# h11-5.net
KiCad netlist of a schematic drawn in EAGLE
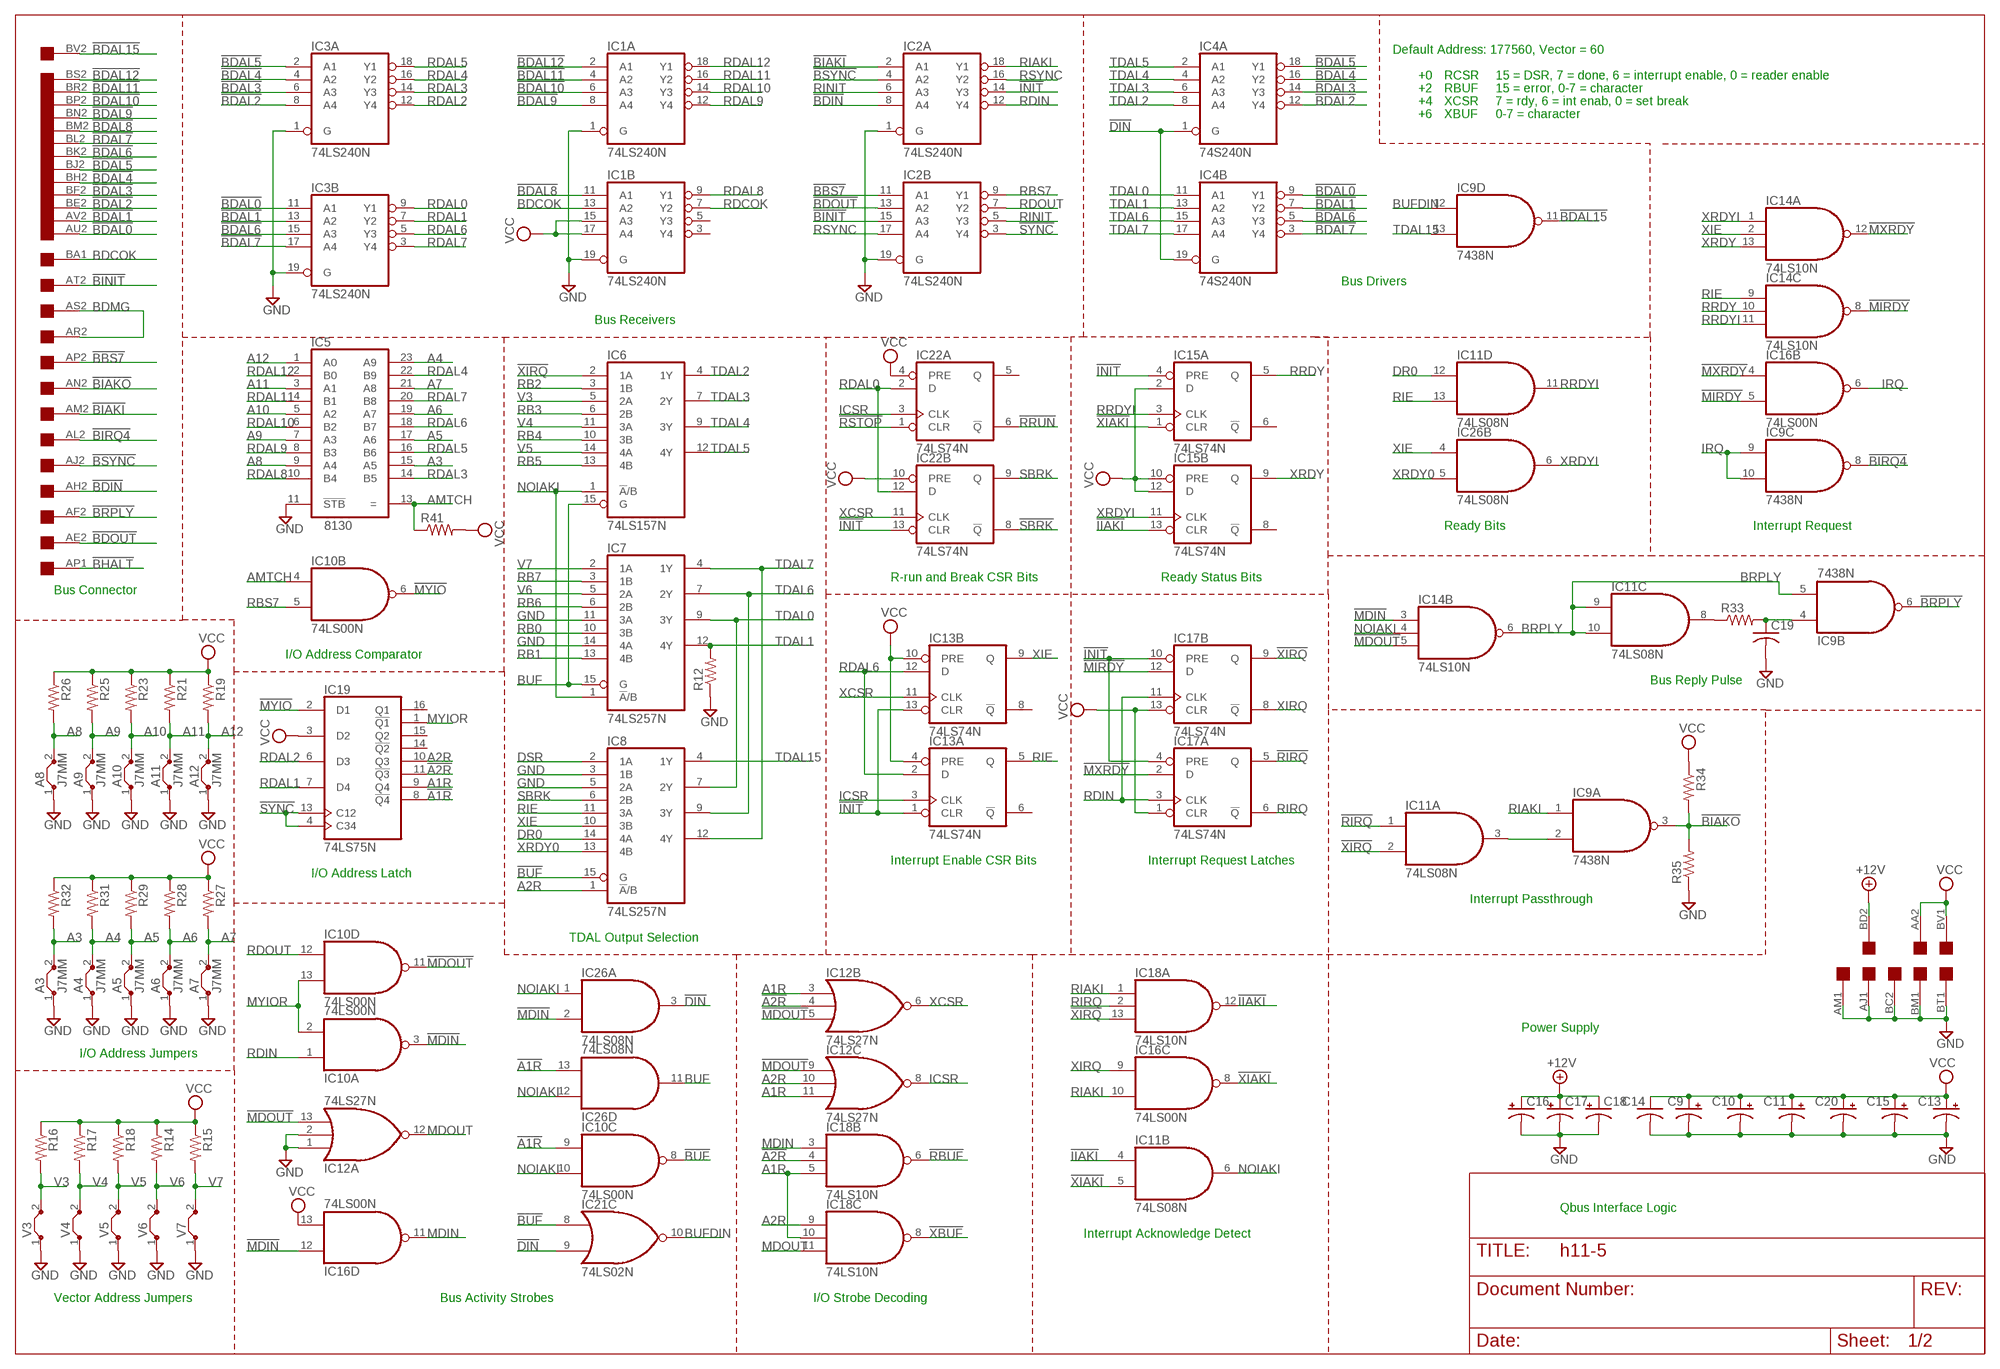
[diagram p0: schematic, sheet 1]
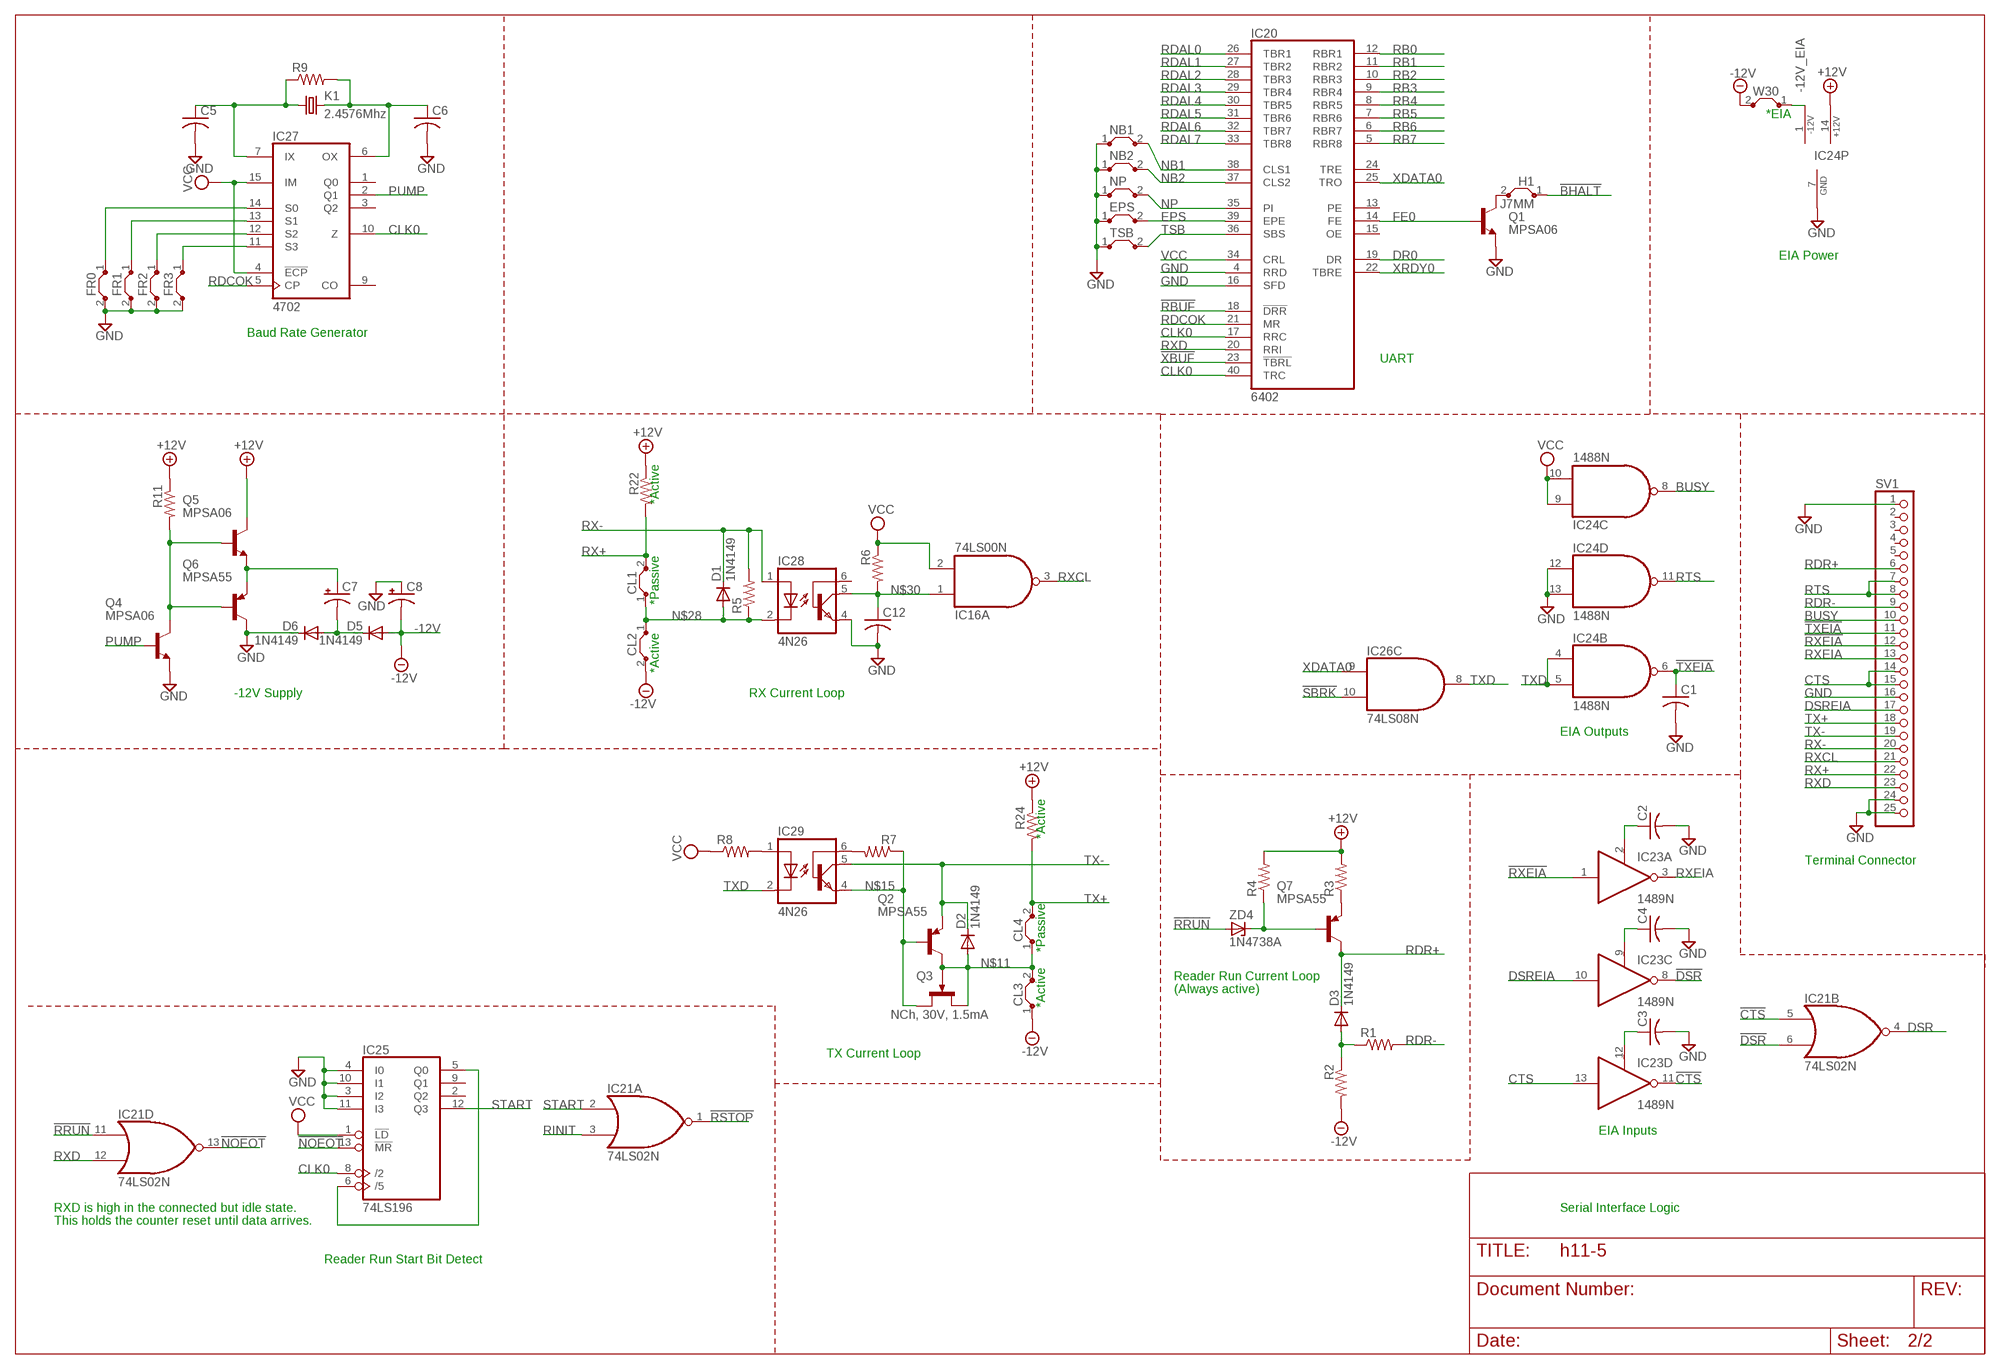
[diagram p1: schematic, sheet 2]

(export (version "E")
  (design (tool "Eeschema 10.0.6"))
  (components
    (comp (ref "C1")
      (value "C-US075-032X103")
      (footprint "eagle-import:C075-032X103")
      (libsource (lib "eagle-import") (part "C-US075-032X103"))
    )
    (comp (ref "C2")
      (value "C-US075-032X103")
      (footprint "eagle-import:C075-032X103")
      (libsource (lib "eagle-import") (part "C-US075-032X103"))
    )
    (comp (ref "C3")
      (value "C-US075-032X103")
      (footprint "eagle-import:C075-032X103")
      (libsource (lib "eagle-import") (part "C-US075-032X103"))
    )
    (comp (ref "C4")
      (value "C-US075-032X103")
      (footprint "eagle-import:C075-032X103")
      (libsource (lib "eagle-import") (part "C-US075-032X103"))
    )
    (comp (ref "C5")
      (value "C-US075-032X103")
      (footprint "eagle-import:C075-032X103")
      (libsource (lib "eagle-import") (part "C-US075-032X103"))
    )
    (comp (ref "C6")
      (value "C-US075-032X103")
      (footprint "eagle-import:C075-032X103")
      (libsource (lib "eagle-import") (part "C-US075-032X103"))
    )
    (comp (ref "C7")
      (value "CPOL-USB45181B")
      (footprint "eagle-import:B45181B")
      (libsource (lib "eagle-import") (part "CPOL-USB45181B"))
    )
    (comp (ref "C8")
      (value "CPOL-USB45181B")
      (footprint "eagle-import:B45181B")
      (libsource (lib "eagle-import") (part "CPOL-USB45181B"))
    )
    (comp (ref "C12")
      (value "C-US075-032X103")
      (footprint "eagle-import:C075-032X103")
      (libsource (lib "eagle-import") (part "C-US075-032X103"))
    )
    (comp (ref "CL1")
      (value "J7MM")
      (footprint "eagle-import:07")
      (libsource (lib "eagle-import") (part "J7MM"))
    )
    (comp (ref "CL2")
      (value "J7MM")
      (footprint "eagle-import:07")
      (libsource (lib "eagle-import") (part "J7MM"))
    )
    (comp (ref "CL3")
      (value "J7MM")
      (footprint "eagle-import:07")
      (libsource (lib "eagle-import") (part "J7MM"))
    )
    (comp (ref "CL4")
      (value "J7MM")
      (footprint "eagle-import:07")
      (libsource (lib "eagle-import") (part "J7MM"))
    )
    (comp (ref "D1")
      (value "1N4149")
      (footprint "eagle-import:DO35-10")
      (libsource (lib "eagle-import") (part "1N4148DO35-10"))
    )
    (comp (ref "D2")
      (value "1N4149")
      (footprint "eagle-import:DO35-10")
      (libsource (lib "eagle-import") (part "1N4148DO35-10"))
    )
    (comp (ref "D3")
      (value "1N4149")
      (footprint "eagle-import:DO35-10")
      (libsource (lib "eagle-import") (part "1N4148DO35-10"))
    )
    (comp (ref "D5")
      (value "1N4149")
      (footprint "eagle-import:DO35-10")
      (libsource (lib "eagle-import") (part "1N4148DO35-10"))
    )
    (comp (ref "D6")
      (value "1N4149")
      (footprint "eagle-import:DO35-10")
      (libsource (lib "eagle-import") (part "1N4148DO35-10"))
    )
    (comp (ref "EPS")
      (value "J7MM")
      (footprint "eagle-import:07")
      (libsource (lib "eagle-import") (part "J7MM"))
    )
    (comp (ref "FR0")
      (value "J7MM")
      (footprint "eagle-import:07")
      (libsource (lib "eagle-import") (part "J7MM"))
    )
    (comp (ref "FR1")
      (value "J7MM")
      (footprint "eagle-import:07")
      (libsource (lib "eagle-import") (part "J7MM"))
    )
    (comp (ref "FR2")
      (value "J7MM")
      (footprint "eagle-import:07")
      (libsource (lib "eagle-import") (part "J7MM"))
    )
    (comp (ref "FR3")
      (value "J7MM")
      (footprint "eagle-import:07")
      (libsource (lib "eagle-import") (part "J7MM"))
    )
    (comp (ref "H1")
      (value "J7MM")
      (footprint "eagle-import:07")
      (libsource (lib "eagle-import") (part "J7MM"))
    )
    (comp (ref "IC16")
      (value "74LS00N")
      (footprint "eagle-import:DIL14")
      (libsource (lib "eagle-import") (part "7400NLS"))
    )
    (comp (ref "IC20")
      (value "6402")
      (footprint "eagle-import:DIL40")
      (libsource (lib "eagle-import") (part "HD6402"))
    )
    (comp (ref "IC21")
      (value "74LS02N")
      (footprint "eagle-import:DIL14")
      (libsource (lib "eagle-import") (part "7402NLS"))
    )
    (comp (ref "IC23")
      (value "1489N")
      (footprint "eagle-import:DIL14")
      (libsource (lib "eagle-import") (part "1489N"))
    )
    (comp (ref "IC24")
      (value "1488N")
      (footprint "eagle-import:DIL14")
      (libsource (lib "eagle-import") (part "1488N"))
    )
    (comp (ref "IC25")
      (value "74LS196")
      (footprint "eagle-import:DIL14")
      (libsource (lib "eagle-import") (part "74LS196"))
    )
    (comp (ref "IC26")
      (value "74LS08N")
      (footprint "eagle-import:DIL14")
      (libsource (lib "eagle-import") (part "7408NLS"))
    )
    (comp (ref "IC27")
      (value "4702")
      (footprint "eagle-import:DIL16")
      (libsource (lib "eagle-import") (part "HD4702"))
    )
    (comp (ref "IC28")
      (value "4N26")
      (footprint "eagle-import:DIL06")
      (fields (field (name "MF") "FAIRCHILD SEMICONDUCTOR") (field (name "MPN") "4N35"))
      (libsource (lib "eagle-import") (part "4N35"))
    )
    (comp (ref "IC29")
      (value "4N26")
      (footprint "eagle-import:DIL06")
      (fields (field (name "MF") "FAIRCHILD SEMICONDUCTOR") (field (name "MPN") "4N35"))
      (libsource (lib "eagle-import") (part "4N35"))
    )
    (comp (ref "K1")
      (value "2.4576Mhz")
      (footprint "eagle-import:HC33U-H")
      (libsource (lib "eagle-import") (part "CRYSTALHC33U-H"))
    )
    (comp (ref "NB1")
      (value "J7MM")
      (footprint "eagle-import:07")
      (libsource (lib "eagle-import") (part "J7MM"))
    )
    (comp (ref "NB2")
      (value "J7MM")
      (footprint "eagle-import:07")
      (libsource (lib "eagle-import") (part "J7MM"))
    )
    (comp (ref "NP")
      (value "J7MM")
      (footprint "eagle-import:07")
      (libsource (lib "eagle-import") (part "J7MM"))
    )
    (comp (ref "Q1")
      (value "MPSA06")
      (footprint "eagle-import:TO92L")
      (libsource (lib "eagle-import") (part "-NPN-TO92L"))
    )
    (comp (ref "Q2")
      (value "MPSA55")
      (footprint "eagle-import:TO92L")
      (libsource (lib "eagle-import") (part "-PNP-TO92L"))
    )
    (comp (ref "Q3")
      (value "NCh, 30V, 1.5mA")
      (footprint "eagle-import:TO18E")
      (libsource (lib "eagle-import") (part "2N4391"))
    )
    (comp (ref "Q4")
      (value "MPSA06")
      (footprint "eagle-import:TO92L")
      (libsource (lib "eagle-import") (part "-NPN-TO92L"))
    )
    (comp (ref "Q5")
      (value "MPSA06")
      (footprint "eagle-import:TO92L")
      (libsource (lib "eagle-import") (part "-NPN-TO92L"))
    )
    (comp (ref "Q6")
      (value "MPSA55")
      (footprint "eagle-import:TO92L")
      (libsource (lib "eagle-import") (part "-PNP-TO92L"))
    )
    (comp (ref "Q7")
      (value "MPSA55")
      (footprint "eagle-import:TO92L")
      (libsource (lib "eagle-import") (part "-PNP-TO92L"))
    )
    (comp (ref "R1")
      (value "R-US_0207/10")
      (footprint "eagle-import:0207_10")
      (libsource (lib "eagle-import") (part "R-US_0207/10"))
    )
    (comp (ref "R2")
      (value "R-US_0207/10")
      (footprint "eagle-import:0207_10")
      (libsource (lib "eagle-import") (part "R-US_0207/10"))
    )
    (comp (ref "R3")
      (value "R-US_0207/10")
      (footprint "eagle-import:0207_10")
      (libsource (lib "eagle-import") (part "R-US_0207/10"))
    )
    (comp (ref "R4")
      (value "R-US_0207/10")
      (footprint "eagle-import:0207_10")
      (libsource (lib "eagle-import") (part "R-US_0207/10"))
    )
    (comp (ref "R5")
      (value "R-US_0207/10")
      (footprint "eagle-import:0207_10")
      (libsource (lib "eagle-import") (part "R-US_0207/10"))
    )
    (comp (ref "R6")
      (value "R-US_0207/10")
      (footprint "eagle-import:0207_10")
      (libsource (lib "eagle-import") (part "R-US_0207/10"))
    )
    (comp (ref "R7")
      (value "R-US_0207/10")
      (footprint "eagle-import:0207_10")
      (libsource (lib "eagle-import") (part "R-US_0207/10"))
    )
    (comp (ref "R8")
      (value "R-US_0207/10")
      (footprint "eagle-import:0207_10")
      (libsource (lib "eagle-import") (part "R-US_0207/10"))
    )
    (comp (ref "R9")
      (value "R-US_0207/10")
      (footprint "eagle-import:0207_10")
      (libsource (lib "eagle-import") (part "R-US_0207/10"))
    )
    (comp (ref "R11")
      (value "R-US_0411/12")
      (footprint "eagle-import:0411_12")
      (libsource (lib "eagle-import") (part "R-US_0411/12"))
    )
    (comp (ref "R22")
      (value "R-US_0207/10")
      (footprint "eagle-import:0207_10")
      (libsource (lib "eagle-import") (part "R-US_0207/10"))
    )
    (comp (ref "R24")
      (value "R-US_0207/10")
      (footprint "eagle-import:0207_10")
      (libsource (lib "eagle-import") (part "R-US_0207/10"))
    )
    (comp (ref "SV1")
      (value "PINHD-1X25")
      (footprint "eagle-import:1X25")
      (libsource (lib "eagle-import") (part "PINHD-1X25"))
    )
    (comp (ref "TSB")
      (value "J7MM")
      (footprint "eagle-import:07")
      (libsource (lib "eagle-import") (part "J7MM"))
    )
    (comp (ref "W30")
      (value "J7MM")
      (footprint "eagle-import:07")
      (libsource (lib "eagle-import") (part "J7MM"))
    )
    (comp (ref "ZD4")
      (value "1N4738A")
      (footprint "eagle-import:DO41Z10")
      (libsource (lib "eagle-import") (part "1N4728"))
    )
    (comp (ref "A3")
      (value "J7MM")
      (footprint "eagle-import:07")
      (libsource (lib "eagle-import") (part "J7MM"))
    )
    (comp (ref "A4")
      (value "J7MM")
      (footprint "eagle-import:07")
      (libsource (lib "eagle-import") (part "J7MM"))
    )
    (comp (ref "A5")
      (value "J7MM")
      (footprint "eagle-import:07")
      (libsource (lib "eagle-import") (part "J7MM"))
    )
    (comp (ref "A6")
      (value "J7MM")
      (footprint "eagle-import:07")
      (libsource (lib "eagle-import") (part "J7MM"))
    )
    (comp (ref "A7")
      (value "J7MM")
      (footprint "eagle-import:07")
      (libsource (lib "eagle-import") (part "J7MM"))
    )
    (comp (ref "A8")
      (value "J7MM")
      (footprint "eagle-import:07")
      (libsource (lib "eagle-import") (part "J7MM"))
    )
    (comp (ref "A9")
      (value "J7MM")
      (footprint "eagle-import:07")
      (libsource (lib "eagle-import") (part "J7MM"))
    )
    (comp (ref "A10")
      (value "J7MM")
      (footprint "eagle-import:07")
      (libsource (lib "eagle-import") (part "J7MM"))
    )
    (comp (ref "A11")
      (value "J7MM")
      (footprint "eagle-import:07")
      (libsource (lib "eagle-import") (part "J7MM"))
    )
    (comp (ref "A12")
      (value "J7MM")
      (footprint "eagle-import:07")
      (libsource (lib "eagle-import") (part "J7MM"))
    )
    (comp (ref "C9")
      (value "CPOL-USB45181B")
      (footprint "eagle-import:B45181B")
      (libsource (lib "eagle-import") (part "CPOL-USB45181B"))
    )
    (comp (ref "C10")
      (value "CPOL-USB45181B")
      (footprint "eagle-import:B45181B")
      (libsource (lib "eagle-import") (part "CPOL-USB45181B"))
    )
    (comp (ref "C11")
      (value "CPOL-USB45181B")
      (footprint "eagle-import:B45181B")
      (libsource (lib "eagle-import") (part "CPOL-USB45181B"))
    )
    (comp (ref "C13")
      (value "CPOL-USB45181B")
      (footprint "eagle-import:B45181B")
      (libsource (lib "eagle-import") (part "CPOL-USB45181B"))
    )
    (comp (ref "C14")
      (value "C-US075-032X103")
      (footprint "eagle-import:C075-032X103")
      (libsource (lib "eagle-import") (part "C-US075-032X103"))
    )
    (comp (ref "C15")
      (value "CPOL-USB45181B")
      (footprint "eagle-import:B45181B")
      (libsource (lib "eagle-import") (part "CPOL-USB45181B"))
    )
    (comp (ref "C16")
      (value "CPOL-USB45181B")
      (footprint "eagle-import:B45181B")
      (libsource (lib "eagle-import") (part "CPOL-USB45181B"))
    )
    (comp (ref "C17")
      (value "CPOL-USB45181B")
      (footprint "eagle-import:B45181B")
      (libsource (lib "eagle-import") (part "CPOL-USB45181B"))
    )
    (comp (ref "C18")
      (value "CPOL-USB45181B")
      (footprint "eagle-import:B45181B")
      (libsource (lib "eagle-import") (part "CPOL-USB45181B"))
    )
    (comp (ref "C19")
      (value "C-US075-032X103")
      (footprint "eagle-import:C075-032X103")
      (libsource (lib "eagle-import") (part "C-US075-032X103"))
    )
    (comp (ref "C20")
      (value "CPOL-USB45181B")
      (footprint "eagle-import:B45181B")
      (libsource (lib "eagle-import") (part "CPOL-USB45181B"))
    )
    (comp (ref "EDGE$")
      (value "DOUBLE")
      (footprint "eagle-import:EDGE-CON4")
      (libsource (lib "eagle-import") (part "DOUBLE"))
    )
    (comp (ref "IC1")
      (value "74LS240N")
      (footprint "eagle-import:DIL20")
      (libsource (lib "eagle-import") (part "74240NLS"))
    )
    (comp (ref "IC2")
      (value "74LS240N")
      (footprint "eagle-import:DIL20")
      (libsource (lib "eagle-import") (part "74240NLS"))
    )
    (comp (ref "IC3")
      (value "74LS240N")
      (footprint "eagle-import:DIL20")
      (libsource (lib "eagle-import") (part "74240NLS"))
    )
    (comp (ref "IC4")
      (value "74S240N")
      (footprint "eagle-import:DIL20")
      (libsource (lib "eagle-import") (part "74240NS"))
    )
    (comp (ref "IC5")
      (value "8130")
      (footprint "eagle-import:DIL24")
      (libsource (lib "eagle-import") (part "8130"))
    )
    (comp (ref "IC6")
      (value "74LS157N")
      (footprint "eagle-import:DIL16")
      (libsource (lib "eagle-import") (part "74157NLS"))
    )
    (comp (ref "IC7")
      (value "74LS257N")
      (footprint "eagle-import:DIL16")
      (libsource (lib "eagle-import") (part "74257NLS"))
    )
    (comp (ref "IC8")
      (value "74LS257N")
      (footprint "eagle-import:DIL16")
      (libsource (lib "eagle-import") (part "74257NLS"))
    )
    (comp (ref "IC9")
      (value "7438N")
      (footprint "eagle-import:DIL14")
      (libsource (lib "eagle-import") (part "7438NLS"))
    )
    (comp (ref "IC10")
      (value "74LS00N")
      (footprint "eagle-import:DIL14")
      (libsource (lib "eagle-import") (part "7400NLS"))
    )
    (comp (ref "IC11")
      (value "74LS08N")
      (footprint "eagle-import:DIL14")
      (libsource (lib "eagle-import") (part "7408NLS"))
    )
    (comp (ref "IC12")
      (value "74LS27N")
      (footprint "eagle-import:DIL14")
      (libsource (lib "eagle-import") (part "7427NLS"))
    )
    (comp (ref "IC13")
      (value "74LS74N")
      (footprint "eagle-import:DIL14")
      (libsource (lib "eagle-import") (part "7474NLS"))
    )
    (comp (ref "IC14")
      (value "74LS10N")
      (footprint "eagle-import:DIL14")
      (libsource (lib "eagle-import") (part "7410NLS"))
    )
    (comp (ref "IC15")
      (value "74LS74N")
      (footprint "eagle-import:DIL14")
      (libsource (lib "eagle-import") (part "7474NLS"))
    )
    (comp (ref "IC17")
      (value "74LS74N")
      (footprint "eagle-import:DIL14")
      (libsource (lib "eagle-import") (part "7474NLS"))
    )
    (comp (ref "IC18")
      (value "74LS10N")
      (footprint "eagle-import:DIL14")
      (libsource (lib "eagle-import") (part "7410NLS"))
    )
    (comp (ref "IC19")
      (value "74LS75N")
      (footprint "eagle-import:DIL16")
      (libsource (lib "eagle-import") (part "7475NLS"))
    )
    (comp (ref "IC22")
      (value "74LS74N")
      (footprint "eagle-import:DIL14")
      (libsource (lib "eagle-import") (part "7474NLS"))
    )
    (comp (ref "R12")
      (value "R-US_0207/10")
      (footprint "eagle-import:0207_10")
      (libsource (lib "eagle-import") (part "R-US_0207/10"))
    )
    (comp (ref "R14")
      (value "R-US_0207/10")
      (footprint "eagle-import:0207_10")
      (libsource (lib "eagle-import") (part "R-US_0207/10"))
    )
    (comp (ref "R15")
      (value "R-US_0207/10")
      (footprint "eagle-import:0207_10")
      (libsource (lib "eagle-import") (part "R-US_0207/10"))
    )
    (comp (ref "R16")
      (value "R-US_0207/10")
      (footprint "eagle-import:0207_10")
      (libsource (lib "eagle-import") (part "R-US_0207/10"))
    )
    (comp (ref "R17")
      (value "R-US_0207/10")
      (footprint "eagle-import:0207_10")
      (libsource (lib "eagle-import") (part "R-US_0207/10"))
    )
    (comp (ref "R18")
      (value "R-US_0207/10")
      (footprint "eagle-import:0207_10")
      (libsource (lib "eagle-import") (part "R-US_0207/10"))
    )
    (comp (ref "R19")
      (value "R-US_0207/10")
      (footprint "eagle-import:0207_10")
      (libsource (lib "eagle-import") (part "R-US_0207/10"))
    )
    (comp (ref "R21")
      (value "R-US_0207/10")
      (footprint "eagle-import:0207_10")
      (libsource (lib "eagle-import") (part "R-US_0207/10"))
    )
    (comp (ref "R23")
      (value "R-US_0207/10")
      (footprint "eagle-import:0207_10")
      (libsource (lib "eagle-import") (part "R-US_0207/10"))
    )
    (comp (ref "R25")
      (value "R-US_0207/10")
      (footprint "eagle-import:0207_10")
      (libsource (lib "eagle-import") (part "R-US_0207/10"))
    )
    (comp (ref "R26")
      (value "R-US_0207/10")
      (footprint "eagle-import:0207_10")
      (libsource (lib "eagle-import") (part "R-US_0207/10"))
    )
    (comp (ref "R27")
      (value "R-US_0207/10")
      (footprint "eagle-import:0207_10")
      (libsource (lib "eagle-import") (part "R-US_0207/10"))
    )
    (comp (ref "R28")
      (value "R-US_0207/10")
      (footprint "eagle-import:0207_10")
      (libsource (lib "eagle-import") (part "R-US_0207/10"))
    )
    (comp (ref "R29")
      (value "R-US_0207/10")
      (footprint "eagle-import:0207_10")
      (libsource (lib "eagle-import") (part "R-US_0207/10"))
    )
    (comp (ref "R31")
      (value "R-US_0207/10")
      (footprint "eagle-import:0207_10")
      (libsource (lib "eagle-import") (part "R-US_0207/10"))
    )
    (comp (ref "R32")
      (value "R-US_0207/10")
      (footprint "eagle-import:0207_10")
      (libsource (lib "eagle-import") (part "R-US_0207/10"))
    )
    (comp (ref "R33")
      (value "R-US_0207/10")
      (footprint "eagle-import:0207_10")
      (libsource (lib "eagle-import") (part "R-US_0207/10"))
    )
    (comp (ref "R34")
      (value "R-US_0207/10")
      (footprint "eagle-import:0207_10")
      (libsource (lib "eagle-import") (part "R-US_0207/10"))
    )
    (comp (ref "R35")
      (value "R-US_0207/10")
      (footprint "eagle-import:0207_10")
      (libsource (lib "eagle-import") (part "R-US_0207/10"))
    )
    (comp (ref "R41")
      (value "R-US_0207/10")
      (footprint "eagle-import:0207_10")
      (libsource (lib "eagle-import") (part "R-US_0207/10"))
    )
    (comp (ref "V3")
      (value "J7MM")
      (footprint "eagle-import:07")
      (libsource (lib "eagle-import") (part "J7MM"))
    )
    (comp (ref "V4")
      (value "J7MM")
      (footprint "eagle-import:07")
      (libsource (lib "eagle-import") (part "J7MM"))
    )
    (comp (ref "V5")
      (value "J7MM")
      (footprint "eagle-import:07")
      (libsource (lib "eagle-import") (part "J7MM"))
    )
    (comp (ref "V6")
      (value "J7MM")
      (footprint "eagle-import:07")
      (libsource (lib "eagle-import") (part "J7MM"))
    )
    (comp (ref "V7")
      (value "J7MM")
      (footprint "eagle-import:07")
      (libsource (lib "eagle-import") (part "J7MM"))
    )
  )
  (nets
    (net (code "1") (name "+12V") (class "Default")
      (node (ref "C16") (pin "+") (pinfunction "+_+") (pintype "passive"))
      (node (ref "C17") (pin "+") (pinfunction "+_+") (pintype "passive"))
      (node (ref "C18") (pin "+") (pinfunction "+_+") (pintype "passive"))
      (node (ref "EDGE$") (pin "BD2") (pinfunction "1_BD2") (pintype "bidirectional"))
      (node (ref "IC24") (pin "14") (pinfunction "+12V_14") (pintype "power_in"))
      (node (ref "Q5") (pin "3") (pinfunction "C_3") (pintype "passive"))
      (node (ref "R11") (pin "1") (pinfunction "1_1") (pintype "passive"))
      (node (ref "R22") (pin "1") (pinfunction "1_1") (pintype "passive"))
      (node (ref "R24") (pin "1") (pinfunction "1_1") (pintype "passive"))
      (node (ref "R3") (pin "2") (pinfunction "2_2") (pintype "passive"))
      (node (ref "R4") (pin "2") (pinfunction "2_2") (pintype "passive"))
    )
    (net (code "2") (name "-12V") (class "Default")
      (node (ref "C8") (pin "-") (pinfunction "-_-") (pintype "passive"))
      (node (ref "CL2") (pin "2") (pinfunction "2_2") (pintype "passive"))
      (node (ref "CL3") (pin "1") (pinfunction "1_1") (pintype "passive"))
      (node (ref "D5") (pin "A") (pinfunction "A_A") (pintype "passive"))
      (node (ref "R2") (pin "2") (pinfunction "2_2") (pintype "passive"))
      (node (ref "W30") (pin "2") (pinfunction "2_2") (pintype "passive"))
    )
    (net (code "3") (name "-12V_EIA") (class "Default")
      (node (ref "IC24") (pin "1") (pinfunction "-12V_1") (pintype "power_in"))
      (node (ref "W30") (pin "1") (pinfunction "1_1") (pintype "passive"))
    )
    (net (code "4") (name "A1R") (class "Default")
      (node (ref "IC12") (pin "11") (pinfunction "I2_11") (pintype "input"))
      (node (ref "IC12") (pin "3") (pinfunction "I0_3") (pintype "input"))
      (node (ref "IC18") (pin "10") (pinfunction "I1_10") (pintype "input"))
      (node (ref "IC18") (pin "5") (pinfunction "I2_5") (pintype "input"))
      (node (ref "IC19") (pin "9") (pinfunction "Q4_9") (pintype "output"))
    )
    (net (code "5") (name "A2R") (class "Default")
      (node (ref "IC12") (pin "10") (pinfunction "I1_10") (pintype "input"))
      (node (ref "IC18") (pin "9") (pinfunction "I0_9") (pintype "input"))
      (node (ref "IC19") (pin "10") (pinfunction "Q3_10") (pintype "output"))
      (node (ref "IC8") (pin "1") (pinfunction "~{A}/B_1") (pintype "input"))
    )
    (net (code "6") (name "A3") (class "Default")
      (node (ref "A3") (pin "2") (pinfunction "2_2") (pintype "passive"))
      (node (ref "IC5") (pin "15") (pinfunction "A5_15") (pintype "input"))
      (node (ref "R32") (pin "2") (pinfunction "2_2") (pintype "passive"))
    )
    (net (code "7") (name "A4") (class "Default")
      (node (ref "A4") (pin "2") (pinfunction "2_2") (pintype "passive"))
      (node (ref "IC5") (pin "23") (pinfunction "A9_23") (pintype "input"))
      (node (ref "R31") (pin "2") (pinfunction "2_2") (pintype "passive"))
    )
    (net (code "8") (name "A5") (class "Default")
      (node (ref "A5") (pin "2") (pinfunction "2_2") (pintype "passive"))
      (node (ref "IC5") (pin "17") (pinfunction "A6_17") (pintype "input"))
      (node (ref "R29") (pin "2") (pinfunction "2_2") (pintype "passive"))
    )
    (net (code "9") (name "A6") (class "Default")
      (node (ref "A6") (pin "2") (pinfunction "2_2") (pintype "passive"))
      (node (ref "IC5") (pin "19") (pinfunction "A7_19") (pintype "input"))
      (node (ref "R28") (pin "2") (pinfunction "2_2") (pintype "passive"))
    )
    (net (code "10") (name "A7") (class "Default")
      (node (ref "A7") (pin "2") (pinfunction "2_2") (pintype "passive"))
      (node (ref "IC5") (pin "21") (pinfunction "A8_21") (pintype "input"))
      (node (ref "R27") (pin "2") (pinfunction "2_2") (pintype "passive"))
    )
    (net (code "11") (name "A8") (class "Default")
      (node (ref "A8") (pin "2") (pinfunction "2_2") (pintype "passive"))
      (node (ref "IC5") (pin "9") (pinfunction "A4_9") (pintype "input"))
      (node (ref "R26") (pin "2") (pinfunction "2_2") (pintype "passive"))
    )
    (net (code "12") (name "A9") (class "Default")
      (node (ref "A9") (pin "2") (pinfunction "2_2") (pintype "passive"))
      (node (ref "IC5") (pin "7") (pinfunction "A3_7") (pintype "input"))
      (node (ref "R25") (pin "2") (pinfunction "2_2") (pintype "passive"))
    )
    (net (code "13") (name "A10") (class "Default")
      (node (ref "A10") (pin "2") (pinfunction "2_2") (pintype "passive"))
      (node (ref "IC5") (pin "5") (pinfunction "A2_5") (pintype "input"))
      (node (ref "R23") (pin "2") (pinfunction "2_2") (pintype "passive"))
    )
    (net (code "14") (name "A11") (class "Default")
      (node (ref "A11") (pin "2") (pinfunction "2_2") (pintype "passive"))
      (node (ref "IC5") (pin "3") (pinfunction "A1_3") (pintype "input"))
      (node (ref "R21") (pin "2") (pinfunction "2_2") (pintype "passive"))
    )
    (net (code "15") (name "A12") (class "Default")
      (node (ref "A12") (pin "2") (pinfunction "2_2") (pintype "passive"))
      (node (ref "IC5") (pin "1") (pinfunction "A0_1") (pintype "input"))
      (node (ref "R19") (pin "2") (pinfunction "2_2") (pintype "passive"))
    )
    (net (code "16") (name "AMTCH") (class "Default")
      (node (ref "IC10") (pin "4") (pinfunction "I0_4") (pintype "input"))
      (node (ref "IC5") (pin "13") (pinfunction "=_13") (pintype "output"))
      (node (ref "R41") (pin "1") (pinfunction "1_1") (pintype "passive"))
    )
    (net (code "17") (name "BDCOK") (class "Default")
      (node (ref "EDGE$") (pin "BA1") (pinfunction "1_BA1") (pintype "bidirectional"))
      (node (ref "IC1") (pin "13") (pinfunction "A2_13") (pintype "input"))
    )
    (net (code "18") (name "BDMG") (class "Default")
      (node (ref "EDGE$") (pin "AR2") (pinfunction "1_AR2") (pintype "bidirectional"))
      (node (ref "EDGE$") (pin "AS2") (pinfunction "1_AS2") (pintype "bidirectional"))
    )
    (net (code "19") (name "BRPLY") (class "Default")
      (node (ref "IC11") (pin "10") (pinfunction "I1_10") (pintype "input"))
      (node (ref "IC11") (pin "9") (pinfunction "I0_9") (pintype "input"))
      (node (ref "IC14") (pin "6") (pinfunction "O_6") (pintype "output"))
      (node (ref "IC9") (pin "5") (pinfunction "I1_5") (pintype "input"))
    )
    (net (code "20") (name "BUF") (class "Default")
      (node (ref "IC26") (pin "11") (pinfunction "O_11") (pintype "output"))
      (node (ref "IC6") (pin "15") (pinfunction "G_15") (pintype "input"))
      (node (ref "IC7") (pin "15") (pinfunction "G_15") (pintype "input"))
    )
    (net (code "21") (name "BUFDIN") (class "Default")
      (node (ref "IC21") (pin "10") (pinfunction "O_10") (pintype "output"))
      (node (ref "IC9") (pin "12") (pinfunction "I0_12") (pintype "input"))
    )
    (net (code "22") (name "BUSY") (class "Default")
      (node (ref "IC24") (pin "8") (pinfunction "O_8") (pintype "output"))
      (node (ref "SV1") (pin "10") (pinfunction "10_10") (pintype "passive"))
    )
    (net (code "23") (name "CLK0") (class "Default")
      (node (ref "IC20") (pin "17") (pinfunction "RRC_17") (pintype "input"))
      (node (ref "IC20") (pin "40") (pinfunction "TRC_40") (pintype "input"))
      (node (ref "IC25") (pin "8") (pinfunction "/2_8") (pintype "bidirectional"))
      (node (ref "IC27") (pin "10") (pinfunction "Z_10") (pintype "output"))
    )
    (net (code "24") (name "CTS") (class "Default")
      (node (ref "IC23") (pin "13") (pinfunction "I_13") (pintype "input"))
      (node (ref "SV1") (pin "14") (pinfunction "14_14") (pintype "passive"))
      (node (ref "SV1") (pin "15") (pinfunction "15_15") (pintype "passive"))
    )
    (net (code "25") (name "DR0") (class "Default")
      (node (ref "IC11") (pin "12") (pinfunction "I0_12") (pintype "input"))
      (node (ref "IC20") (pin "19") (pinfunction "DR_19") (pintype "tri_state"))
      (node (ref "IC8") (pin "14") (pinfunction "4A_14") (pintype "input"))
    )
    (net (code "26") (name "DSR") (class "Default")
      (node (ref "IC21") (pin "4") (pinfunction "O_4") (pintype "output"))
      (node (ref "IC8") (pin "2") (pinfunction "1A_2") (pintype "input"))
    )
    (net (code "27") (name "DSREIA") (class "Default")
      (node (ref "IC23") (pin "10") (pinfunction "I_10") (pintype "input"))
      (node (ref "SV1") (pin "17") (pinfunction "17_17") (pintype "passive"))
    )
    (net (code "28") (name "EPS") (class "Default")
      (node (ref "EPS") (pin "2") (pinfunction "2_2") (pintype "passive"))
      (node (ref "IC20") (pin "39") (pinfunction "EPE_39") (pintype "input"))
    )
    (net (code "29") (name "FE0") (class "Default")
      (node (ref "IC20") (pin "14") (pinfunction "FE_14") (pintype "tri_state"))
      (node (ref "Q1") (pin "2") (pinfunction "B_2") (pintype "passive"))
    )
    (net (code "30") (name "GND") (class "Default")
      (node (ref "A10") (pin "1") (pinfunction "1_1") (pintype "passive"))
      (node (ref "A11") (pin "1") (pinfunction "1_1") (pintype "passive"))
      (node (ref "A12") (pin "1") (pinfunction "1_1") (pintype "passive"))
      (node (ref "A3") (pin "1") (pinfunction "1_1") (pintype "passive"))
      (node (ref "A4") (pin "1") (pinfunction "1_1") (pintype "passive"))
      (node (ref "A5") (pin "1") (pinfunction "1_1") (pintype "passive"))
      (node (ref "A6") (pin "1") (pinfunction "1_1") (pintype "passive"))
      (node (ref "A7") (pin "1") (pinfunction "1_1") (pintype "passive"))
      (node (ref "A8") (pin "1") (pinfunction "1_1") (pintype "passive"))
      (node (ref "A9") (pin "1") (pinfunction "1_1") (pintype "passive"))
      (node (ref "C1") (pin "2") (pinfunction "2_2") (pintype "passive"))
      (node (ref "C10") (pin "-") (pinfunction "-_-") (pintype "passive"))
      (node (ref "C11") (pin "-") (pinfunction "-_-") (pintype "passive"))
      (node (ref "C12") (pin "2") (pinfunction "2_2") (pintype "passive"))
      (node (ref "C13") (pin "-") (pinfunction "-_-") (pintype "passive"))
      (node (ref "C14") (pin "2") (pinfunction "2_2") (pintype "passive"))
      (node (ref "C15") (pin "-") (pinfunction "-_-") (pintype "passive"))
      (node (ref "C16") (pin "-") (pinfunction "-_-") (pintype "passive"))
      (node (ref "C17") (pin "-") (pinfunction "-_-") (pintype "passive"))
      (node (ref "C18") (pin "-") (pinfunction "-_-") (pintype "passive"))
      (node (ref "C19") (pin "2") (pinfunction "2_2") (pintype "passive"))
      (node (ref "C2") (pin "2") (pinfunction "2_2") (pintype "passive"))
      (node (ref "C20") (pin "-") (pinfunction "-_-") (pintype "passive"))
      (node (ref "C3") (pin "2") (pinfunction "2_2") (pintype "passive"))
      (node (ref "C4") (pin "2") (pinfunction "2_2") (pintype "passive"))
      (node (ref "C5") (pin "2") (pinfunction "2_2") (pintype "passive"))
      (node (ref "C6") (pin "2") (pinfunction "2_2") (pintype "passive"))
      (node (ref "C8") (pin "+") (pinfunction "+_+") (pintype "passive"))
      (node (ref "C9") (pin "-") (pinfunction "-_-") (pintype "passive"))
      (node (ref "D6") (pin "C") (pinfunction "C_C") (pintype "passive"))
      (node (ref "EDGE$") (pin "AJ1") (pinfunction "1_AJ1") (pintype "bidirectional"))
      (node (ref "EDGE$") (pin "AM1") (pinfunction "1_AM1") (pintype "bidirectional"))
      (node (ref "EDGE$") (pin "BC2") (pinfunction "1_BC2") (pintype "bidirectional"))
      (node (ref "EDGE$") (pin "BM1") (pinfunction "1_BM1") (pintype "bidirectional"))
      (node (ref "EDGE$") (pin "BT1") (pinfunction "1_BT1") (pintype "bidirectional"))
      (node (ref "EPS") (pin "1") (pinfunction "1_1") (pintype "passive"))
      (node (ref "FR0") (pin "2") (pinfunction "2_2") (pintype "passive"))
      (node (ref "FR1") (pin "2") (pinfunction "2_2") (pintype "passive"))
      (node (ref "FR2") (pin "2") (pinfunction "2_2") (pintype "passive"))
      (node (ref "FR3") (pin "2") (pinfunction "2_2") (pintype "passive"))
      (node (ref "IC1") (pin "1") (pinfunction "G_1") (pintype "input"))
      (node (ref "IC1") (pin "19") (pinfunction "G_19") (pintype "input"))
      (node (ref "IC12") (pin "1") (pinfunction "I0_1") (pintype "input"))
      (node (ref "IC12") (pin "2") (pinfunction "I1_2") (pintype "input"))
      (node (ref "IC2") (pin "1") (pinfunction "G_1") (pintype "input"))
      (node (ref "IC2") (pin "19") (pinfunction "G_19") (pintype "input"))
      (node (ref "IC20") (pin "16") (pinfunction "SFD_16") (pintype "input"))
      (node (ref "IC20") (pin "4") (pinfunction "RRD_4") (pintype "input"))
      (node (ref "IC24") (pin "12") (pinfunction "I0_12") (pintype "input"))
      (node (ref "IC24") (pin "13") (pinfunction "I1_13") (pintype "input"))
      (node (ref "IC24") (pin "7") (pinfunction "GND_7") (pintype "power_in"))
      (node (ref "IC25") (pin "10") (pinfunction "I1_10") (pintype "input"))
      (node (ref "IC25") (pin "11") (pinfunction "I3_11") (pintype "input"))
      (node (ref "IC25") (pin "3") (pinfunction "I2_3") (pintype "input"))
      (node (ref "IC25") (pin "4") (pinfunction "I0_4") (pintype "input"))
      (node (ref "IC28") (pin "4") (pinfunction "EMI_4") (pintype "passive"))
      (node (ref "IC3") (pin "1") (pinfunction "G_1") (pintype "input"))
      (node (ref "IC3") (pin "19") (pinfunction "G_19") (pintype "input"))
      (node (ref "IC5") (pin "11") (pinfunction "~{STB}_11") (pintype "input"))
      (node (ref "IC7") (pin "11") (pinfunction "3A_11") (pintype "input"))
      (node (ref "IC7") (pin "14") (pinfunction "4A_14") (pintype "input"))
      (node (ref "IC8") (pin "3") (pinfunction "1B_3") (pintype "input"))
      (node (ref "IC8") (pin "5") (pinfunction "2A_5") (pintype "input"))
      (node (ref "NB1") (pin "1") (pinfunction "1_1") (pintype "passive"))
      (node (ref "NB2") (pin "1") (pinfunction "1_1") (pintype "passive"))
      (node (ref "NP") (pin "1") (pinfunction "1_1") (pintype "passive"))
      (node (ref "Q1") (pin "1") (pinfunction "E_1") (pintype "passive"))
      (node (ref "Q4") (pin "1") (pinfunction "E_1") (pintype "passive"))
      (node (ref "Q6") (pin "3") (pinfunction "C_3") (pintype "passive"))
      (node (ref "R12") (pin "1") (pinfunction "1_1") (pintype "passive"))
      (node (ref "R35") (pin "1") (pinfunction "1_1") (pintype "passive"))
      (node (ref "SV1") (pin "1") (pinfunction "1_1") (pintype "passive"))
      (node (ref "SV1") (pin "16") (pinfunction "16_16") (pintype "passive"))
      (node (ref "SV1") (pin "24") (pinfunction "24_24") (pintype "passive"))
      (node (ref "SV1") (pin "25") (pinfunction "25_25") (pintype "passive"))
      (node (ref "TSB") (pin "1") (pinfunction "1_1") (pintype "passive"))
      (node (ref "V3") (pin "1") (pinfunction "1_1") (pintype "passive"))
      (node (ref "V4") (pin "1") (pinfunction "1_1") (pintype "passive"))
      (node (ref "V5") (pin "1") (pinfunction "1_1") (pintype "passive"))
      (node (ref "V6") (pin "1") (pinfunction "1_1") (pintype "passive"))
      (node (ref "V7") (pin "1") (pinfunction "1_1") (pintype "passive"))
    )
    (net (code "31") (name "ICSR") (class "Default")
      (node (ref "IC12") (pin "8") (pinfunction "O_8") (pintype "output"))
      (node (ref "IC13") (pin "3") (pinfunction "CLK_3") (pintype "input"))
      (node (ref "IC22") (pin "3") (pinfunction "CLK_3") (pintype "input"))
    )
    (net (code "32") (name "IRQ") (class "Default")
      (node (ref "IC16") (pin "6") (pinfunction "O_6") (pintype "output"))
      (node (ref "IC9") (pin "10") (pinfunction "I1_10") (pintype "input"))
      (node (ref "IC9") (pin "9") (pinfunction "I0_9") (pintype "input"))
    )
    (net (code "33") (name "MDIN") (class "Default")
      (node (ref "IC16") (pin "11") (pinfunction "O_11") (pintype "output"))
      (node (ref "IC18") (pin "3") (pinfunction "I0_3") (pintype "input"))
    )
    (net (code "34") (name "MDOUT") (class "Default")
      (node (ref "IC12") (pin "12") (pinfunction "O_12") (pintype "output"))
      (node (ref "IC18") (pin "11") (pinfunction "I2_11") (pintype "input"))
    )
    (net (code "35") (name "MYIOR") (class "Default")
      (node (ref "IC10") (pin "13") (pinfunction "I1_13") (pintype "input"))
      (node (ref "IC10") (pin "2") (pinfunction "I1_2") (pintype "input"))
      (node (ref "IC19") (pin "1") (pinfunction "~{Q1}_1") (pintype "output"))
    )
    (net (code "36") (name "N$11") (class "Default")
      (node (ref "CL3") (pin "2") (pinfunction "2_2") (pintype "passive"))
      (node (ref "CL4") (pin "1") (pinfunction "1_1") (pintype "passive"))
      (node (ref "D2") (pin "A") (pinfunction "A_A") (pintype "passive"))
      (node (ref "Q2") (pin "3") (pinfunction "C_3") (pintype "passive"))
      (node (ref "Q3") (pin "D") (pinfunction "D_D") (pintype "passive"))
      (node (ref "Q3") (pin "G") (pinfunction "G_G") (pintype "passive"))
    )
    (net (code "37") (name "N$15") (class "Default")
      (node (ref "IC29") (pin "4") (pinfunction "EMI_4") (pintype "passive"))
      (node (ref "Q2") (pin "2") (pinfunction "B_2") (pintype "passive"))
      (node (ref "Q3") (pin "S") (pinfunction "S_S") (pintype "passive"))
      (node (ref "R7") (pin "1") (pinfunction "1_1") (pintype "passive"))
    )
    (net (code "38") (name "N$28") (class "Default")
      (node (ref "CL1") (pin "1") (pinfunction "1_1") (pintype "passive"))
      (node (ref "CL2") (pin "1") (pinfunction "1_1") (pintype "passive"))
      (node (ref "D1") (pin "A") (pinfunction "A_A") (pintype "passive"))
      (node (ref "IC28") (pin "2") (pinfunction "C_2") (pintype "passive"))
      (node (ref "R5") (pin "1") (pinfunction "1_1") (pintype "passive"))
    )
    (net (code "39") (name "N$30") (class "Default")
      (node (ref "C12") (pin "1") (pinfunction "1_1") (pintype "passive"))
      (node (ref "IC16") (pin "1") (pinfunction "I0_1") (pintype "input"))
      (node (ref "IC28") (pin "5") (pinfunction "COL_5") (pintype "passive"))
      (node (ref "R6") (pin "2") (pinfunction "2_2") (pintype "passive"))
    )
    (net (code "40") (name "NB1") (class "Default")
      (node (ref "IC20") (pin "38") (pinfunction "CLS1_38") (pintype "input"))
      (node (ref "NB1") (pin "2") (pinfunction "2_2") (pintype "passive"))
    )
    (net (code "41") (name "NB2") (class "Default")
      (node (ref "IC20") (pin "37") (pinfunction "CLS2_37") (pintype "input"))
      (node (ref "NB2") (pin "2") (pinfunction "2_2") (pintype "passive"))
    )
    (net (code "42") (name "NOIAKI") (class "Default")
      (node (ref "IC10") (pin "10") (pinfunction "I1_10") (pintype "input"))
      (node (ref "IC11") (pin "6") (pinfunction "O_6") (pintype "output"))
      (node (ref "IC14") (pin "4") (pinfunction "I1_4") (pintype "input"))
      (node (ref "IC26") (pin "1") (pinfunction "I0_1") (pintype "input"))
      (node (ref "IC26") (pin "12") (pinfunction "I0_12") (pintype "input"))
      (node (ref "IC6") (pin "1") (pinfunction "~{A}/B_1") (pintype "input"))
      (node (ref "IC7") (pin "1") (pinfunction "~{A}/B_1") (pintype "input"))
    )
    (net (code "43") (name "NP") (class "Default")
      (node (ref "IC20") (pin "35") (pinfunction "PI_35") (pintype "input"))
      (node (ref "NP") (pin "2") (pinfunction "2_2") (pintype "passive"))
    )
    (net (code "44") (name "Net-(C7-Pad-)") (class "Default")
      (node (ref "C7") (pin "-") (pinfunction "-_-") (pintype "passive"))
      (node (ref "D5") (pin "C") (pinfunction "C_C") (pintype "passive"))
      (node (ref "D6") (pin "A") (pinfunction "A_A") (pintype "passive"))
    )
    (net (code "45") (name "Net-(D3-PadA)") (class "Default")
      (node (ref "D3") (pin "A") (pinfunction "A_A") (pintype "passive"))
      (node (ref "R1") (pin "1") (pinfunction "1_1") (pintype "passive"))
      (node (ref "R2") (pin "1") (pinfunction "1_1") (pintype "passive"))
    )
    (net (code "46") (name "Net-(IC9B-I0)") (class "Default")
      (node (ref "C19") (pin "1") (pinfunction "1_1") (pintype "passive"))
      (node (ref "IC9") (pin "4") (pinfunction "I0_4") (pintype "input"))
      (node (ref "R33") (pin "2") (pinfunction "2_2") (pintype "passive"))
    )
    (net (code "47") (name "Net-(IC11A-O)") (class "Default")
      (node (ref "IC11") (pin "3") (pinfunction "O_3") (pintype "output"))
      (node (ref "IC9") (pin "2") (pinfunction "I1_2") (pintype "input"))
    )
    (net (code "48") (name "Net-(IC11C-O)") (class "Default")
      (node (ref "IC11") (pin "8") (pinfunction "O_8") (pintype "output"))
      (node (ref "R33") (pin "1") (pinfunction "1_1") (pintype "passive"))
    )
    (net (code "49") (name "Net-(IC23A-RC)") (class "Default")
      (node (ref "C2") (pin "1") (pinfunction "1_1") (pintype "passive"))
      (node (ref "IC23") (pin "2") (pinfunction "RC_2") (pintype "input"))
    )
    (net (code "50") (name "Net-(IC23C-RC)") (class "Default")
      (node (ref "C4") (pin "1") (pinfunction "1_1") (pintype "passive"))
      (node (ref "IC23") (pin "9") (pinfunction "RC_9") (pintype "input"))
    )
    (net (code "51") (name "Net-(IC23D-RC)") (class "Default")
      (node (ref "C3") (pin "1") (pinfunction "1_1") (pintype "passive"))
      (node (ref "IC23") (pin "12") (pinfunction "RC_12") (pintype "input"))
    )
    (net (code "52") (name "Net-(IC25A-Q0)") (class "Default")
      (node (ref "IC25") (pin "5") (pinfunction "Q0_5") (pintype "output"))
      (node (ref "IC25") (pin "6") (pinfunction "/5_6") (pintype "bidirectional"))
    )
    (net (code "53") (name "Net-(IC27A-IX)") (class "Default")
      (node (ref "C5") (pin "1") (pinfunction "1_1") (pintype "passive"))
      (node (ref "IC27") (pin "7") (pinfunction "IX_7") (pintype "input"))
      (node (ref "K1") (pin "1") (pinfunction "1_1") (pintype "passive"))
      (node (ref "R9") (pin "1") (pinfunction "1_1") (pintype "passive"))
    )
    (net (code "54") (name "Net-(IC27A-OX)") (class "Default")
      (node (ref "C6") (pin "1") (pinfunction "1_1") (pintype "passive"))
      (node (ref "IC27") (pin "6") (pinfunction "OX_6") (pintype "output"))
      (node (ref "K1") (pin "2") (pinfunction "2_2") (pintype "passive"))
      (node (ref "R9") (pin "2") (pinfunction "2_2") (pintype "passive"))
    )
    (net (code "55") (name "Net-(IC27A-S0)") (class "Default")
      (node (ref "FR0") (pin "1") (pinfunction "1_1") (pintype "passive"))
      (node (ref "IC27") (pin "14") (pinfunction "S0_14") (pintype "input"))
    )
    (net (code "56") (name "Net-(IC27A-S1)") (class "Default")
      (node (ref "FR1") (pin "1") (pinfunction "1_1") (pintype "passive"))
      (node (ref "IC27") (pin "13") (pinfunction "S1_13") (pintype "input"))
    )
    (net (code "57") (name "Net-(IC27A-S2)") (class "Default")
      (node (ref "FR2") (pin "1") (pinfunction "1_1") (pintype "passive"))
      (node (ref "IC27") (pin "12") (pinfunction "S2_12") (pintype "input"))
    )
    (net (code "58") (name "Net-(IC27A-S3)") (class "Default")
      (node (ref "FR3") (pin "1") (pinfunction "1_1") (pintype "passive"))
      (node (ref "IC27") (pin "11") (pinfunction "S3_11") (pintype "input"))
    )
    (net (code "59") (name "Net-(IC29-A)") (class "Default")
      (node (ref "IC29") (pin "1") (pinfunction "A_1") (pintype "passive"))
      (node (ref "R8") (pin "2") (pinfunction "2_2") (pintype "passive"))
    )
    (net (code "60") (name "Net-(IC29-BAS)") (class "Default")
      (node (ref "IC29") (pin "6") (pinfunction "BAS_6") (pintype "passive"))
      (node (ref "R7") (pin "2") (pinfunction "2_2") (pintype "passive"))
    )
    (net (code "61") (name "Net-(Q1-C)") (class "Default")
      (node (ref "H1") (pin "2") (pinfunction "2_2") (pintype "passive"))
      (node (ref "Q1") (pin "3") (pinfunction "C_3") (pintype "passive"))
    )
    (net (code "62") (name "Net-(Q4-C)") (class "Default")
      (node (ref "Q4") (pin "3") (pinfunction "C_3") (pintype "passive"))
      (node (ref "Q5") (pin "2") (pinfunction "B_2") (pintype "passive"))
      (node (ref "Q6") (pin "2") (pinfunction "B_2") (pintype "passive"))
      (node (ref "R11") (pin "2") (pinfunction "2_2") (pintype "passive"))
    )
    (net (code "63") (name "Net-(Q5-E)") (class "Default")
      (node (ref "C7") (pin "+") (pinfunction "+_+") (pintype "passive"))
      (node (ref "Q5") (pin "1") (pinfunction "E_1") (pintype "passive"))
      (node (ref "Q6") (pin "1") (pinfunction "E_1") (pintype "passive"))
    )
    (net (code "64") (name "Net-(Q7-B)") (class "Default")
      (node (ref "Q7") (pin "2") (pinfunction "B_2") (pintype "passive"))
      (node (ref "R4") (pin "1") (pinfunction "1_1") (pintype "passive"))
      (node (ref "ZD4") (pin "C") (pinfunction "C_C") (pintype "passive"))
    )
    (net (code "65") (name "Net-(Q7-E)") (class "Default")
      (node (ref "Q7") (pin "1") (pinfunction "E_1") (pintype "passive"))
      (node (ref "R3") (pin "1") (pinfunction "1_1") (pintype "passive"))
    )
    (net (code "66") (name "PUMP") (class "Default")
      (node (ref "IC27") (pin "2") (pinfunction "Q1_2") (pintype "output"))
      (node (ref "Q4") (pin "2") (pinfunction "B_2") (pintype "passive"))
    )
    (net (code "67") (name "RB0") (class "Default")
      (node (ref "IC20") (pin "12") (pinfunction "RBR1_12") (pintype "tri_state"))
      (node (ref "IC7") (pin "10") (pinfunction "3B_10") (pintype "input"))
    )
    (net (code "68") (name "RB1") (class "Default")
      (node (ref "IC20") (pin "11") (pinfunction "RBR2_11") (pintype "tri_state"))
      (node (ref "IC7") (pin "13") (pinfunction "4B_13") (pintype "input"))
    )
    (net (code "69") (name "RB2") (class "Default")
      (node (ref "IC20") (pin "10") (pinfunction "RBR3_10") (pintype "tri_state"))
      (node (ref "IC6") (pin "3") (pinfunction "1B_3") (pintype "input"))
    )
    (net (code "70") (name "RB3") (class "Default")
      (node (ref "IC20") (pin "9") (pinfunction "RBR4_9") (pintype "tri_state"))
      (node (ref "IC6") (pin "6") (pinfunction "2B_6") (pintype "input"))
    )
    (net (code "71") (name "RB4") (class "Default")
      (node (ref "IC20") (pin "8") (pinfunction "RBR5_8") (pintype "tri_state"))
      (node (ref "IC6") (pin "10") (pinfunction "3B_10") (pintype "input"))
    )
    (net (code "72") (name "RB5") (class "Default")
      (node (ref "IC20") (pin "7") (pinfunction "RBR6_7") (pintype "tri_state"))
      (node (ref "IC6") (pin "13") (pinfunction "4B_13") (pintype "input"))
    )
    (net (code "73") (name "RB6") (class "Default")
      (node (ref "IC20") (pin "6") (pinfunction "RBR7_6") (pintype "tri_state"))
      (node (ref "IC7") (pin "6") (pinfunction "2B_6") (pintype "input"))
    )
    (net (code "74") (name "RB7") (class "Default")
      (node (ref "IC20") (pin "5") (pinfunction "RBR8_5") (pintype "tri_state"))
      (node (ref "IC7") (pin "3") (pinfunction "1B_3") (pintype "input"))
    )
    (net (code "75") (name "RBS7") (class "Default")
      (node (ref "IC10") (pin "5") (pinfunction "I1_5") (pintype "input"))
      (node (ref "IC2") (pin "9") (pinfunction "Y1_9") (pintype "tri_state"))
    )
    (net (code "76") (name "RDAL0") (class "Default")
      (node (ref "IC20") (pin "26") (pinfunction "TBR1_26") (pintype "input"))
      (node (ref "IC22") (pin "12") (pinfunction "D_12") (pintype "input"))
      (node (ref "IC22") (pin "2") (pinfunction "D_2") (pintype "input"))
      (node (ref "IC3") (pin "9") (pinfunction "Y1_9") (pintype "tri_state"))
    )
    (net (code "77") (name "RDAL1") (class "Default")
      (node (ref "IC19") (pin "7") (pinfunction "D4_7") (pintype "input"))
      (node (ref "IC20") (pin "27") (pinfunction "TBR2_27") (pintype "input"))
      (node (ref "IC3") (pin "7") (pinfunction "Y2_7") (pintype "tri_state"))
    )
    (net (code "78") (name "RDAL2") (class "Default")
      (node (ref "IC19") (pin "6") (pinfunction "D3_6") (pintype "input"))
      (node (ref "IC20") (pin "28") (pinfunction "TBR3_28") (pintype "input"))
      (node (ref "IC3") (pin "12") (pinfunction "Y4_12") (pintype "tri_state"))
    )
    (net (code "79") (name "RDAL3") (class "Default")
      (node (ref "IC20") (pin "29") (pinfunction "TBR4_29") (pintype "input"))
      (node (ref "IC3") (pin "14") (pinfunction "Y3_14") (pintype "tri_state"))
      (node (ref "IC5") (pin "14") (pinfunction "B5_14") (pintype "input"))
    )
    (net (code "80") (name "RDAL4") (class "Default")
      (node (ref "IC20") (pin "30") (pinfunction "TBR5_30") (pintype "input"))
      (node (ref "IC3") (pin "16") (pinfunction "Y2_16") (pintype "tri_state"))
      (node (ref "IC5") (pin "22") (pinfunction "B9_22") (pintype "input"))
    )
    (net (code "81") (name "RDAL5") (class "Default")
      (node (ref "IC20") (pin "31") (pinfunction "TBR6_31") (pintype "input"))
      (node (ref "IC3") (pin "18") (pinfunction "Y1_18") (pintype "tri_state"))
      (node (ref "IC5") (pin "16") (pinfunction "B6_16") (pintype "input"))
    )
    (net (code "82") (name "RDAL6") (class "Default")
      (node (ref "IC13") (pin "12") (pinfunction "D_12") (pintype "input"))
      (node (ref "IC13") (pin "2") (pinfunction "D_2") (pintype "input"))
      (node (ref "IC20") (pin "32") (pinfunction "TBR7_32") (pintype "input"))
      (node (ref "IC3") (pin "5") (pinfunction "Y3_5") (pintype "tri_state"))
      (node (ref "IC5") (pin "18") (pinfunction "B7_18") (pintype "input"))
    )
    (net (code "83") (name "RDAL7") (class "Default")
      (node (ref "IC20") (pin "33") (pinfunction "TBR8_33") (pintype "input"))
      (node (ref "IC3") (pin "3") (pinfunction "Y4_3") (pintype "tri_state"))
      (node (ref "IC5") (pin "20") (pinfunction "B8_20") (pintype "input"))
    )
    (net (code "84") (name "RDAL8") (class "Default")
      (node (ref "IC1") (pin "9") (pinfunction "Y1_9") (pintype "tri_state"))
      (node (ref "IC5") (pin "10") (pinfunction "B4_10") (pintype "input"))
    )
    (net (code "85") (name "RDAL9") (class "Default")
      (node (ref "IC1") (pin "12") (pinfunction "Y4_12") (pintype "tri_state"))
      (node (ref "IC5") (pin "8") (pinfunction "B3_8") (pintype "input"))
    )
    (net (code "86") (name "RDAL10") (class "Default")
      (node (ref "IC1") (pin "14") (pinfunction "Y3_14") (pintype "tri_state"))
      (node (ref "IC5") (pin "6") (pinfunction "B2_6") (pintype "input"))
    )
    (net (code "87") (name "RDAL11") (class "Default")
      (node (ref "IC1") (pin "16") (pinfunction "Y2_16") (pintype "tri_state"))
      (node (ref "IC5") (pin "4") (pinfunction "B1_4") (pintype "input"))
    )
    (net (code "88") (name "RDAL12") (class "Default")
      (node (ref "IC1") (pin "18") (pinfunction "Y1_18") (pintype "tri_state"))
      (node (ref "IC5") (pin "2") (pinfunction "B0_2") (pintype "input"))
    )
    (net (code "89") (name "RDCOK") (class "Default")
      (node (ref "IC1") (pin "7") (pinfunction "Y2_7") (pintype "tri_state"))
      (node (ref "IC20") (pin "21") (pinfunction "MR_21") (pintype "input"))
      (node (ref "IC27") (pin "5") (pinfunction "CP_5") (pintype "input"))
    )
    (net (code "90") (name "RDIN") (class "Default")
      (node (ref "IC10") (pin "1") (pinfunction "I0_1") (pintype "input"))
      (node (ref "IC17") (pin "11") (pinfunction "CLK_11") (pintype "input"))
      (node (ref "IC17") (pin "3") (pinfunction "CLK_3") (pintype "input"))
      (node (ref "IC2") (pin "12") (pinfunction "Y4_12") (pintype "tri_state"))
    )
    (net (code "91") (name "RDOUT") (class "Default")
      (node (ref "IC10") (pin "12") (pinfunction "I0_12") (pintype "input"))
      (node (ref "IC2") (pin "7") (pinfunction "Y2_7") (pintype "tri_state"))
    )
    (net (code "92") (name "RDR+") (class "Default")
      (node (ref "D3") (pin "C") (pinfunction "C_C") (pintype "passive"))
      (node (ref "Q7") (pin "3") (pinfunction "C_3") (pintype "passive"))
      (node (ref "SV1") (pin "6") (pinfunction "6_6") (pintype "passive"))
    )
    (net (code "93") (name "RDR-") (class "Default")
      (node (ref "R1") (pin "2") (pinfunction "2_2") (pintype "passive"))
      (node (ref "SV1") (pin "9") (pinfunction "9_9") (pintype "passive"))
    )
    (net (code "94") (name "RIAKI") (class "Default")
      (node (ref "IC16") (pin "10") (pinfunction "I1_10") (pintype "input"))
      (node (ref "IC18") (pin "1") (pinfunction "I0_1") (pintype "input"))
      (node (ref "IC2") (pin "18") (pinfunction "Y1_18") (pintype "tri_state"))
      (node (ref "IC9") (pin "1") (pinfunction "I0_1") (pintype "input"))
    )
    (net (code "95") (name "RIE") (class "Default")
      (node (ref "IC11") (pin "13") (pinfunction "I1_13") (pintype "input"))
      (node (ref "IC13") (pin "5") (pinfunction "Q_5") (pintype "output"))
      (node (ref "IC14") (pin "9") (pinfunction "I0_9") (pintype "input"))
      (node (ref "IC8") (pin "11") (pinfunction "3A_11") (pintype "input"))
    )
    (net (code "96") (name "RINIT") (class "Default")
      (node (ref "IC2") (pin "5") (pinfunction "Y3_5") (pintype "tri_state"))
      (node (ref "IC2") (pin "6") (pinfunction "A3_6") (pintype "input"))
      (node (ref "IC21") (pin "3") (pinfunction "I1_3") (pintype "input"))
    )
    (net (code "97") (name "RIRQ") (class "Default")
      (node (ref "IC17") (pin "6") (pinfunction "~{Q}_6") (pintype "output"))
      (node (ref "IC18") (pin "2") (pinfunction "I1_2") (pintype "input"))
    )
    (net (code "98") (name "RRDY") (class "Default")
      (node (ref "IC14") (pin "10") (pinfunction "I1_10") (pintype "input"))
      (node (ref "IC15") (pin "5") (pinfunction "Q_5") (pintype "output"))
    )
    (net (code "99") (name "RRDYI") (class "Default")
      (node (ref "IC11") (pin "11") (pinfunction "O_11") (pintype "output"))
      (node (ref "IC14") (pin "11") (pinfunction "I2_11") (pintype "input"))
      (node (ref "IC15") (pin "3") (pinfunction "CLK_3") (pintype "input"))
    )
    (net (code "100") (name "RSYNC") (class "Default")
      (node (ref "IC2") (pin "16") (pinfunction "Y2_16") (pintype "tri_state"))
      (node (ref "IC2") (pin "17") (pinfunction "A4_17") (pintype "input"))
    )
    (net (code "101") (name "RTS") (class "Default")
      (node (ref "IC24") (pin "11") (pinfunction "O_11") (pintype "output"))
      (node (ref "SV1") (pin "7") (pinfunction "7_7") (pintype "passive"))
      (node (ref "SV1") (pin "8") (pinfunction "8_8") (pintype "passive"))
    )
    (net (code "102") (name "RX+") (class "Default")
      (node (ref "CL1") (pin "2") (pinfunction "2_2") (pintype "passive"))
      (node (ref "R22") (pin "2") (pinfunction "2_2") (pintype "passive"))
      (node (ref "SV1") (pin "22") (pinfunction "22_22") (pintype "passive"))
    )
    (net (code "103") (name "RX-") (class "Default")
      (node (ref "D1") (pin "C") (pinfunction "C_C") (pintype "passive"))
      (node (ref "IC28") (pin "1") (pinfunction "A_1") (pintype "passive"))
      (node (ref "R5") (pin "2") (pinfunction "2_2") (pintype "passive"))
      (node (ref "SV1") (pin "20") (pinfunction "20_20") (pintype "passive"))
    )
    (net (code "104") (name "RXCL") (class "Default")
      (node (ref "IC16") (pin "3") (pinfunction "O_3") (pintype "output"))
      (node (ref "SV1") (pin "21") (pinfunction "21_21") (pintype "passive"))
    )
    (net (code "105") (name "RXD") (class "Default")
      (node (ref "IC20") (pin "20") (pinfunction "RRI_20") (pintype "input"))
      (node (ref "IC21") (pin "12") (pinfunction "I1_12") (pintype "input"))
      (node (ref "SV1") (pin "23") (pinfunction "23_23") (pintype "passive"))
    )
    (net (code "106") (name "RXEIA") (class "Default")
      (node (ref "IC23") (pin "3") (pinfunction "O_3") (pintype "output"))
      (node (ref "SV1") (pin "13") (pinfunction "13_13") (pintype "passive"))
    )
    (net (code "107") (name "SBRK") (class "Default")
      (node (ref "IC22") (pin "9") (pinfunction "Q_9") (pintype "output"))
      (node (ref "IC8") (pin "6") (pinfunction "2B_6") (pintype "input"))
    )
    (net (code "108") (name "START") (class "Default")
      (node (ref "IC21") (pin "2") (pinfunction "I0_2") (pintype "input"))
      (node (ref "IC25") (pin "12") (pinfunction "Q3_12") (pintype "output"))
    )
    (net (code "109") (name "TDAL0") (class "Default")
      (node (ref "IC4") (pin "11") (pinfunction "A1_11") (pintype "input"))
      (node (ref "IC7") (pin "9") (pinfunction "3Y_9") (pintype "tri_state"))
      (node (ref "IC8") (pin "7") (pinfunction "2Y_7") (pintype "tri_state"))
    )
    (net (code "110") (name "TDAL1") (class "Default")
      (node (ref "IC4") (pin "13") (pinfunction "A2_13") (pintype "input"))
      (node (ref "IC7") (pin "12") (pinfunction "4Y_12") (pintype "tri_state"))
      (node (ref "R12") (pin "2") (pinfunction "2_2") (pintype "passive"))
    )
    (net (code "111") (name "TDAL2") (class "Default")
      (node (ref "IC4") (pin "8") (pinfunction "A4_8") (pintype "input"))
      (node (ref "IC6") (pin "4") (pinfunction "1Y_4") (pintype "output"))
    )
    (net (code "112") (name "TDAL3") (class "Default")
      (node (ref "IC4") (pin "6") (pinfunction "A3_6") (pintype "input"))
      (node (ref "IC6") (pin "7") (pinfunction "2Y_7") (pintype "output"))
    )
    (net (code "113") (name "TDAL4") (class "Default")
      (node (ref "IC4") (pin "4") (pinfunction "A2_4") (pintype "input"))
      (node (ref "IC6") (pin "9") (pinfunction "3Y_9") (pintype "output"))
    )
    (net (code "114") (name "TDAL5") (class "Default")
      (node (ref "IC4") (pin "2") (pinfunction "A1_2") (pintype "input"))
      (node (ref "IC6") (pin "12") (pinfunction "4Y_12") (pintype "output"))
    )
    (net (code "115") (name "TDAL6") (class "Default")
      (node (ref "IC4") (pin "15") (pinfunction "A3_15") (pintype "input"))
      (node (ref "IC7") (pin "7") (pinfunction "2Y_7") (pintype "tri_state"))
      (node (ref "IC8") (pin "9") (pinfunction "3Y_9") (pintype "tri_state"))
    )
    (net (code "116") (name "TDAL7") (class "Default")
      (node (ref "IC4") (pin "17") (pinfunction "A4_17") (pintype "input"))
      (node (ref "IC7") (pin "4") (pinfunction "1Y_4") (pintype "tri_state"))
      (node (ref "IC8") (pin "12") (pinfunction "4Y_12") (pintype "tri_state"))
    )
    (net (code "117") (name "TDAL15") (class "Default")
      (node (ref "IC8") (pin "4") (pinfunction "1Y_4") (pintype "tri_state"))
      (node (ref "IC9") (pin "13") (pinfunction "I1_13") (pintype "input"))
    )
    (net (code "118") (name "TSB") (class "Default")
      (node (ref "IC20") (pin "36") (pinfunction "SBS_36") (pintype "input"))
      (node (ref "TSB") (pin "2") (pinfunction "2_2") (pintype "passive"))
    )
    (net (code "119") (name "TX+") (class "Default")
      (node (ref "CL4") (pin "2") (pinfunction "2_2") (pintype "passive"))
      (node (ref "R24") (pin "2") (pinfunction "2_2") (pintype "passive"))
      (node (ref "SV1") (pin "18") (pinfunction "18_18") (pintype "passive"))
    )
    (net (code "120") (name "TX-") (class "Default")
      (node (ref "D2") (pin "C") (pinfunction "C_C") (pintype "passive"))
      (node (ref "IC29") (pin "5") (pinfunction "COL_5") (pintype "passive"))
      (node (ref "Q2") (pin "1") (pinfunction "E_1") (pintype "passive"))
      (node (ref "SV1") (pin "19") (pinfunction "19_19") (pintype "passive"))
    )
    (net (code "121") (name "TXD") (class "Default")
      (node (ref "IC24") (pin "4") (pinfunction "I0_4") (pintype "input"))
      (node (ref "IC24") (pin "5") (pinfunction "I1_5") (pintype "input"))
      (node (ref "IC26") (pin "8") (pinfunction "O_8") (pintype "output"))
      (node (ref "IC29") (pin "2") (pinfunction "C_2") (pintype "passive"))
    )
    (net (code "122") (name "V3") (class "Default")
      (node (ref "IC6") (pin "5") (pinfunction "2A_5") (pintype "input"))
      (node (ref "R16") (pin "2") (pinfunction "2_2") (pintype "passive"))
      (node (ref "V3") (pin "2") (pinfunction "2_2") (pintype "passive"))
    )
    (net (code "123") (name "V4") (class "Default")
      (node (ref "IC6") (pin "11") (pinfunction "3A_11") (pintype "input"))
      (node (ref "R17") (pin "2") (pinfunction "2_2") (pintype "passive"))
      (node (ref "V4") (pin "2") (pinfunction "2_2") (pintype "passive"))
    )
    (net (code "124") (name "V5") (class "Default")
      (node (ref "IC6") (pin "14") (pinfunction "4A_14") (pintype "input"))
      (node (ref "R18") (pin "2") (pinfunction "2_2") (pintype "passive"))
      (node (ref "V5") (pin "2") (pinfunction "2_2") (pintype "passive"))
    )
    (net (code "125") (name "V6") (class "Default")
      (node (ref "IC7") (pin "5") (pinfunction "2A_5") (pintype "input"))
      (node (ref "R14") (pin "2") (pinfunction "2_2") (pintype "passive"))
      (node (ref "V6") (pin "2") (pinfunction "2_2") (pintype "passive"))
    )
    (net (code "126") (name "V7") (class "Default")
      (node (ref "IC7") (pin "2") (pinfunction "1A_2") (pintype "input"))
      (node (ref "R15") (pin "2") (pinfunction "2_2") (pintype "passive"))
      (node (ref "V7") (pin "2") (pinfunction "2_2") (pintype "passive"))
    )
    (net (code "127") (name "VCC") (class "Default")
      (node (ref "C10") (pin "+") (pinfunction "+_+") (pintype "passive"))
      (node (ref "C11") (pin "+") (pinfunction "+_+") (pintype "passive"))
      (node (ref "C13") (pin "+") (pinfunction "+_+") (pintype "passive"))
      (node (ref "C14") (pin "1") (pinfunction "1_1") (pintype "passive"))
      (node (ref "C15") (pin "+") (pinfunction "+_+") (pintype "passive"))
      (node (ref "C20") (pin "+") (pinfunction "+_+") (pintype "passive"))
      (node (ref "C9") (pin "+") (pinfunction "+_+") (pintype "passive"))
      (node (ref "EDGE$") (pin "AA2") (pinfunction "1_AA2") (pintype "bidirectional"))
      (node (ref "EDGE$") (pin "BV1") (pinfunction "1_BV1") (pintype "bidirectional"))
      (node (ref "IC1") (pin "15") (pinfunction "A3_15") (pintype "input"))
      (node (ref "IC1") (pin "17") (pinfunction "A4_17") (pintype "input"))
      (node (ref "IC13") (pin "10") (pinfunction "PRE_10") (pintype "input"))
      (node (ref "IC13") (pin "4") (pinfunction "PRE_4") (pintype "input"))
      (node (ref "IC15") (pin "10") (pinfunction "PRE_10") (pintype "input"))
      (node (ref "IC15") (pin "12") (pinfunction "D_12") (pintype "input"))
      (node (ref "IC15") (pin "2") (pinfunction "D_2") (pintype "input"))
      (node (ref "IC16") (pin "13") (pinfunction "I1_13") (pintype "input"))
      (node (ref "IC16") (pin "2") (pinfunction "I1_2") (pintype "input"))
      (node (ref "IC17") (pin "1") (pinfunction "CLR_1") (pintype "input"))
      (node (ref "IC17") (pin "13") (pinfunction "CLR_13") (pintype "input"))
      (node (ref "IC19") (pin "3") (pinfunction "D2_3") (pintype "input"))
      (node (ref "IC20") (pin "34") (pinfunction "CRL_34") (pintype "input"))
      (node (ref "IC22") (pin "10") (pinfunction "PRE_10") (pintype "input"))
      (node (ref "IC22") (pin "4") (pinfunction "PRE_4") (pintype "input"))
      (node (ref "IC24") (pin "10") (pinfunction "I1_10") (pintype "input"))
      (node (ref "IC24") (pin "9") (pinfunction "I0_9") (pintype "input"))
      (node (ref "IC25") (pin "1") (pinfunction "~{LD}_1") (pintype "input"))
      (node (ref "IC27") (pin "15") (pinfunction "IM_15") (pintype "input"))
      (node (ref "IC27") (pin "4") (pinfunction "~{ECP}_4") (pintype "input"))
      (node (ref "R14") (pin "1") (pinfunction "1_1") (pintype "passive"))
      (node (ref "R15") (pin "1") (pinfunction "1_1") (pintype "passive"))
      (node (ref "R16") (pin "1") (pinfunction "1_1") (pintype "passive"))
      (node (ref "R17") (pin "1") (pinfunction "1_1") (pintype "passive"))
      (node (ref "R18") (pin "1") (pinfunction "1_1") (pintype "passive"))
      (node (ref "R19") (pin "1") (pinfunction "1_1") (pintype "passive"))
      (node (ref "R21") (pin "1") (pinfunction "1_1") (pintype "passive"))
      (node (ref "R23") (pin "1") (pinfunction "1_1") (pintype "passive"))
      (node (ref "R25") (pin "1") (pinfunction "1_1") (pintype "passive"))
      (node (ref "R26") (pin "1") (pinfunction "1_1") (pintype "passive"))
      (node (ref "R27") (pin "1") (pinfunction "1_1") (pintype "passive"))
      (node (ref "R28") (pin "1") (pinfunction "1_1") (pintype "passive"))
      (node (ref "R29") (pin "1") (pinfunction "1_1") (pintype "passive"))
      (node (ref "R31") (pin "1") (pinfunction "1_1") (pintype "passive"))
      (node (ref "R32") (pin "1") (pinfunction "1_1") (pintype "passive"))
      (node (ref "R34") (pin "1") (pinfunction "1_1") (pintype "passive"))
      (node (ref "R41") (pin "2") (pinfunction "2_2") (pintype "passive"))
      (node (ref "R6") (pin "1") (pinfunction "1_1") (pintype "passive"))
      (node (ref "R8") (pin "1") (pinfunction "1_1") (pintype "passive"))
    )
    (net (code "128") (name "XCSR") (class "Default")
      (node (ref "IC12") (pin "6") (pinfunction "O_6") (pintype "output"))
      (node (ref "IC13") (pin "11") (pinfunction "CLK_11") (pintype "input"))
      (node (ref "IC22") (pin "11") (pinfunction "CLK_11") (pintype "input"))
    )
    (net (code "129") (name "XDATA0") (class "Default")
      (node (ref "IC20") (pin "25") (pinfunction "TRO_25") (pintype "output"))
      (node (ref "IC26") (pin "9") (pinfunction "I0_9") (pintype "input"))
    )
    (net (code "130") (name "XIE") (class "Default")
      (node (ref "IC13") (pin "9") (pinfunction "Q_9") (pintype "output"))
      (node (ref "IC14") (pin "2") (pinfunction "I1_2") (pintype "input"))
      (node (ref "IC26") (pin "4") (pinfunction "I0_4") (pintype "input"))
      (node (ref "IC8") (pin "10") (pinfunction "3B_10") (pintype "input"))
    )
    (net (code "131") (name "XIRQ") (class "Default")
      (node (ref "IC16") (pin "9") (pinfunction "I0_9") (pintype "input"))
      (node (ref "IC17") (pin "8") (pinfunction "~{Q}_8") (pintype "output"))
    )
    (net (code "132") (name "XRDY") (class "Default")
      (node (ref "IC14") (pin "13") (pinfunction "I2_13") (pintype "input"))
      (node (ref "IC15") (pin "9") (pinfunction "Q_9") (pintype "output"))
    )
    (net (code "133") (name "XRDY0") (class "Default")
      (node (ref "IC20") (pin "22") (pinfunction "TBRE_22") (pintype "tri_state"))
      (node (ref "IC26") (pin "5") (pinfunction "I1_5") (pintype "input"))
      (node (ref "IC8") (pin "13") (pinfunction "4B_13") (pintype "input"))
    )
    (net (code "134") (name "XRDYI") (class "Default")
      (node (ref "IC14") (pin "1") (pinfunction "I0_1") (pintype "input"))
      (node (ref "IC15") (pin "11") (pinfunction "CLK_11") (pintype "input"))
      (node (ref "IC26") (pin "6") (pinfunction "O_6") (pintype "output"))
    )
    (net (code "135") (name "unconnected-(IC1B-Y3-Pad5)") (class "Default")
      (node (ref "IC1") (pin "5") (pinfunction "Y3_5") (pintype "tri_state"))
    )
    (net (code "136") (name "unconnected-(IC1B-Y4-Pad3)") (class "Default")
      (node (ref "IC1") (pin "3") (pinfunction "Y4_3") (pintype "tri_state"))
    )
    (net (code "137") (name "unconnected-(IC13A-~{Q}-Pad6)") (class "Default")
      (node (ref "IC13") (pin "6") (pinfunction "~{Q}_6") (pintype "output"))
    )
    (net (code "138") (name "unconnected-(IC13B-~{Q}-Pad8)") (class "Default")
      (node (ref "IC13") (pin "8") (pinfunction "~{Q}_8") (pintype "output"))
    )
    (net (code "139") (name "unconnected-(IC15A-~{Q}-Pad6)") (class "Default")
      (node (ref "IC15") (pin "6") (pinfunction "~{Q}_6") (pintype "output"))
    )
    (net (code "140") (name "unconnected-(IC15B-~{Q}-Pad8)") (class "Default")
      (node (ref "IC15") (pin "8") (pinfunction "~{Q}_8") (pintype "output"))
    )
    (net (code "141") (name "unconnected-(IC19A-Q1-Pad16)") (class "Default")
      (node (ref "IC19") (pin "16") (pinfunction "Q1_16") (pintype "output"))
    )
    (net (code "142") (name "unconnected-(IC19A-Q2-Pad15)") (class "Default")
      (node (ref "IC19") (pin "15") (pinfunction "Q2_15") (pintype "output"))
    )
    (net (code "143") (name "unconnected-(IC19A-~{Q2}-Pad14)") (class "Default")
      (node (ref "IC19") (pin "14") (pinfunction "~{Q2}_14") (pintype "output"))
    )
    (net (code "144") (name "unconnected-(IC20A-OE-Pad15)") (class "Default")
      (node (ref "IC20") (pin "15") (pinfunction "OE_15") (pintype "tri_state"))
    )
    (net (code "145") (name "unconnected-(IC20A-PE-Pad13)") (class "Default")
      (node (ref "IC20") (pin "13") (pinfunction "PE_13") (pintype "tri_state"))
    )
    (net (code "146") (name "unconnected-(IC20A-TRE-Pad24)") (class "Default")
      (node (ref "IC20") (pin "24") (pinfunction "TRE_24") (pintype "output"))
    )
    (net (code "147") (name "unconnected-(IC22A-Q-Pad5)") (class "Default")
      (node (ref "IC22") (pin "5") (pinfunction "Q_5") (pintype "output"))
    )
    (net (code "148") (name "unconnected-(IC25A-Q1-Pad9)") (class "Default")
      (node (ref "IC25") (pin "9") (pinfunction "Q1_9") (pintype "output"))
    )
    (net (code "149") (name "unconnected-(IC25A-Q2-Pad2)") (class "Default")
      (node (ref "IC25") (pin "2") (pinfunction "Q2_2") (pintype "output"))
    )
    (net (code "150") (name "unconnected-(IC27A-CO-Pad9)") (class "Default")
      (node (ref "IC27") (pin "9") (pinfunction "CO_9") (pintype "output"))
    )
    (net (code "151") (name "unconnected-(IC27A-Q0-Pad1)") (class "Default")
      (node (ref "IC27") (pin "1") (pinfunction "Q0_1") (pintype "output"))
    )
    (net (code "152") (name "unconnected-(IC27A-Q2-Pad3)") (class "Default")
      (node (ref "IC27") (pin "3") (pinfunction "Q2_3") (pintype "output"))
    )
    (net (code "153") (name "unconnected-(IC28-BAS-Pad6)") (class "Default")
      (node (ref "IC28") (pin "6") (pinfunction "BAS_6") (pintype "passive"))
    )
    (net (code "154") (name "unconnected-(SV1-Pad2)") (class "Default")
      (node (ref "SV1") (pin "2") (pinfunction "2_2") (pintype "passive"))
    )
    (net (code "155") (name "unconnected-(SV1-Pad3)") (class "Default")
      (node (ref "SV1") (pin "3") (pinfunction "3_3") (pintype "passive"))
    )
    (net (code "156") (name "unconnected-(SV1-Pad4)") (class "Default")
      (node (ref "SV1") (pin "4") (pinfunction "4_4") (pintype "passive"))
    )
    (net (code "157") (name "unconnected-(SV1-Pad5)") (class "Default")
      (node (ref "SV1") (pin "5") (pinfunction "5_5") (pintype "passive"))
    )
    (net (code "158") (name "~{A1R}") (class "Default")
      (node (ref "IC10") (pin "9") (pinfunction "I0_9") (pintype "input"))
      (node (ref "IC19") (pin "8") (pinfunction "~{Q4}_8") (pintype "output"))
      (node (ref "IC26") (pin "13") (pinfunction "I1_13") (pintype "input"))
    )
    (net (code "159") (name "~{A2R}") (class "Default")
      (node (ref "IC12") (pin "4") (pinfunction "I1_4") (pintype "input"))
      (node (ref "IC18") (pin "4") (pinfunction "I1_4") (pintype "input"))
      (node (ref "IC19") (pin "11") (pinfunction "~{Q3}_11") (pintype "output"))
    )
    (net (code "160") (name "~{BBS7}") (class "Default")
      (node (ref "EDGE$") (pin "AP2") (pinfunction "1_AP2") (pintype "bidirectional"))
      (node (ref "IC2") (pin "11") (pinfunction "A1_11") (pintype "input"))
    )
    (net (code "161") (name "~{BDAL0}") (class "Default")
      (node (ref "EDGE$") (pin "AU2") (pinfunction "1_AU2") (pintype "bidirectional"))
      (node (ref "IC3") (pin "11") (pinfunction "A1_11") (pintype "input"))
      (node (ref "IC4") (pin "9") (pinfunction "Y1_9") (pintype "tri_state"))
    )
    (net (code "162") (name "~{BDAL1}") (class "Default")
      (node (ref "EDGE$") (pin "AV2") (pinfunction "1_AV2") (pintype "bidirectional"))
      (node (ref "IC3") (pin "13") (pinfunction "A2_13") (pintype "input"))
      (node (ref "IC4") (pin "7") (pinfunction "Y2_7") (pintype "tri_state"))
    )
    (net (code "163") (name "~{BDAL2}") (class "Default")
      (node (ref "EDGE$") (pin "BE2") (pinfunction "1_BE2") (pintype "bidirectional"))
      (node (ref "IC3") (pin "8") (pinfunction "A4_8") (pintype "input"))
      (node (ref "IC4") (pin "12") (pinfunction "Y4_12") (pintype "tri_state"))
    )
    (net (code "164") (name "~{BDAL3}") (class "Default")
      (node (ref "EDGE$") (pin "BF2") (pinfunction "1_BF2") (pintype "bidirectional"))
      (node (ref "IC3") (pin "6") (pinfunction "A3_6") (pintype "input"))
      (node (ref "IC4") (pin "14") (pinfunction "Y3_14") (pintype "tri_state"))
    )
    (net (code "165") (name "~{BDAL4}") (class "Default")
      (node (ref "EDGE$") (pin "BH2") (pinfunction "1_BH2") (pintype "bidirectional"))
      (node (ref "IC3") (pin "4") (pinfunction "A2_4") (pintype "input"))
      (node (ref "IC4") (pin "16") (pinfunction "Y2_16") (pintype "tri_state"))
    )
    (net (code "166") (name "~{BDAL5}") (class "Default")
      (node (ref "EDGE$") (pin "BJ2") (pinfunction "1_BJ2") (pintype "bidirectional"))
      (node (ref "IC3") (pin "2") (pinfunction "A1_2") (pintype "input"))
      (node (ref "IC4") (pin "18") (pinfunction "Y1_18") (pintype "tri_state"))
    )
    (net (code "167") (name "~{BDAL6}") (class "Default")
      (node (ref "EDGE$") (pin "BK2") (pinfunction "1_BK2") (pintype "bidirectional"))
      (node (ref "IC3") (pin "15") (pinfunction "A3_15") (pintype "input"))
      (node (ref "IC4") (pin "5") (pinfunction "Y3_5") (pintype "tri_state"))
    )
    (net (code "168") (name "~{BDAL7}") (class "Default")
      (node (ref "EDGE$") (pin "BL2") (pinfunction "1_BL2") (pintype "bidirectional"))
      (node (ref "IC3") (pin "17") (pinfunction "A4_17") (pintype "input"))
      (node (ref "IC4") (pin "3") (pinfunction "Y4_3") (pintype "tri_state"))
    )
    (net (code "169") (name "~{BDAL8}") (class "Default")
      (node (ref "EDGE$") (pin "BM2") (pinfunction "1_BM2") (pintype "bidirectional"))
      (node (ref "IC1") (pin "11") (pinfunction "A1_11") (pintype "input"))
    )
    (net (code "170") (name "~{BDAL9}") (class "Default")
      (node (ref "EDGE$") (pin "BN2") (pinfunction "1_BN2") (pintype "bidirectional"))
      (node (ref "IC1") (pin "8") (pinfunction "A4_8") (pintype "input"))
    )
    (net (code "171") (name "~{BDAL10}") (class "Default")
      (node (ref "EDGE$") (pin "BP2") (pinfunction "1_BP2") (pintype "bidirectional"))
      (node (ref "IC1") (pin "6") (pinfunction "A3_6") (pintype "input"))
    )
    (net (code "172") (name "~{BDAL11}") (class "Default")
      (node (ref "EDGE$") (pin "BR2") (pinfunction "1_BR2") (pintype "bidirectional"))
      (node (ref "IC1") (pin "4") (pinfunction "A2_4") (pintype "input"))
    )
    (net (code "173") (name "~{BDAL12}") (class "Default")
      (node (ref "EDGE$") (pin "BS2") (pinfunction "1_BS2") (pintype "bidirectional"))
      (node (ref "IC1") (pin "2") (pinfunction "A1_2") (pintype "input"))
    )
    (net (code "174") (name "~{BDAL15}") (class "Default")
      (node (ref "EDGE$") (pin "BV2") (pinfunction "1_BV2") (pintype "bidirectional"))
      (node (ref "IC9") (pin "11") (pinfunction "O_11") (pintype "open_collector"))
    )
    (net (code "175") (name "~{BDIN}") (class "Default")
      (node (ref "EDGE$") (pin "AH2") (pinfunction "1_AH2") (pintype "bidirectional"))
      (node (ref "IC2") (pin "8") (pinfunction "A4_8") (pintype "input"))
    )
    (net (code "176") (name "~{BDOUT}") (class "Default")
      (node (ref "EDGE$") (pin "AE2") (pinfunction "1_AE2") (pintype "bidirectional"))
      (node (ref "IC2") (pin "13") (pinfunction "A2_13") (pintype "input"))
    )
    (net (code "177") (name "~{BHALT}") (class "Default")
      (node (ref "EDGE$") (pin "AP1") (pinfunction "1_AP1") (pintype "bidirectional"))
      (node (ref "H1") (pin "1") (pinfunction "1_1") (pintype "passive"))
    )
    (net (code "178") (name "~{BIAKI}") (class "Default")
      (node (ref "EDGE$") (pin "AM2") (pinfunction "1_AM2") (pintype "bidirectional"))
      (node (ref "IC2") (pin "2") (pinfunction "A1_2") (pintype "input"))
    )
    (net (code "179") (name "~{BIAKO}") (class "Default")
      (node (ref "EDGE$") (pin "AN2") (pinfunction "1_AN2") (pintype "bidirectional"))
      (node (ref "IC9") (pin "3") (pinfunction "O_3") (pintype "open_collector"))
      (node (ref "R34") (pin "2") (pinfunction "2_2") (pintype "passive"))
      (node (ref "R35") (pin "2") (pinfunction "2_2") (pintype "passive"))
    )
    (net (code "180") (name "~{BINIT}") (class "Default")
      (node (ref "EDGE$") (pin "AT2") (pinfunction "1_AT2") (pintype "bidirectional"))
      (node (ref "IC2") (pin "15") (pinfunction "A3_15") (pintype "input"))
    )
    (net (code "181") (name "~{BIRQ4}") (class "Default")
      (node (ref "EDGE$") (pin "AL2") (pinfunction "1_AL2") (pintype "bidirectional"))
      (node (ref "IC9") (pin "8") (pinfunction "O_8") (pintype "open_collector"))
    )
    (net (code "182") (name "~{BRPLY}") (class "Default")
      (node (ref "EDGE$") (pin "AF2") (pinfunction "1_AF2") (pintype "bidirectional"))
      (node (ref "IC9") (pin "6") (pinfunction "O_6") (pintype "open_collector"))
    )
    (net (code "183") (name "~{BSYNC}") (class "Default")
      (node (ref "EDGE$") (pin "AJ2") (pinfunction "1_AJ2") (pintype "bidirectional"))
      (node (ref "IC2") (pin "4") (pinfunction "A2_4") (pintype "input"))
    )
    (net (code "184") (name "~{BUF}") (class "Default")
      (node (ref "IC10") (pin "8") (pinfunction "O_8") (pintype "output"))
      (node (ref "IC21") (pin "8") (pinfunction "I0_8") (pintype "input"))
      (node (ref "IC8") (pin "15") (pinfunction "G_15") (pintype "input"))
    )
    (net (code "185") (name "~{CTS}") (class "Default")
      (node (ref "IC21") (pin "5") (pinfunction "I0_5") (pintype "input"))
      (node (ref "IC23") (pin "11") (pinfunction "O_11") (pintype "output"))
    )
    (net (code "186") (name "~{DIN}") (class "Default")
      (node (ref "IC21") (pin "9") (pinfunction "I1_9") (pintype "input"))
      (node (ref "IC26") (pin "3") (pinfunction "O_3") (pintype "output"))
      (node (ref "IC4") (pin "1") (pinfunction "G_1") (pintype "input"))
      (node (ref "IC4") (pin "19") (pinfunction "G_19") (pintype "input"))
    )
    (net (code "187") (name "~{DSR}") (class "Default")
      (node (ref "IC21") (pin "6") (pinfunction "I1_6") (pintype "input"))
      (node (ref "IC23") (pin "8") (pinfunction "O_8") (pintype "output"))
    )
    (net (code "188") (name "~{IIAKI}") (class "Default")
      (node (ref "IC11") (pin "4") (pinfunction "I0_4") (pintype "input"))
      (node (ref "IC15") (pin "13") (pinfunction "CLR_13") (pintype "input"))
      (node (ref "IC18") (pin "12") (pinfunction "O_12") (pintype "output"))
    )
    (net (code "189") (name "~{INIT}") (class "Default")
      (node (ref "IC13") (pin "1") (pinfunction "CLR_1") (pintype "input"))
      (node (ref "IC13") (pin "13") (pinfunction "CLR_13") (pintype "input"))
      (node (ref "IC15") (pin "4") (pinfunction "PRE_4") (pintype "input"))
      (node (ref "IC17") (pin "10") (pinfunction "PRE_10") (pintype "input"))
      (node (ref "IC17") (pin "4") (pinfunction "PRE_4") (pintype "input"))
      (node (ref "IC2") (pin "14") (pinfunction "Y3_14") (pintype "tri_state"))
      (node (ref "IC22") (pin "13") (pinfunction "CLR_13") (pintype "input"))
    )
    (net (code "190") (name "~{MDIN}") (class "Default")
      (node (ref "IC10") (pin "3") (pinfunction "O_3") (pintype "output"))
      (node (ref "IC14") (pin "3") (pinfunction "I0_3") (pintype "input"))
      (node (ref "IC16") (pin "12") (pinfunction "I0_12") (pintype "input"))
      (node (ref "IC26") (pin "2") (pinfunction "I1_2") (pintype "input"))
    )
    (net (code "191") (name "~{MDOUT}") (class "Default")
      (node (ref "IC10") (pin "11") (pinfunction "O_11") (pintype "output"))
      (node (ref "IC12") (pin "13") (pinfunction "I2_13") (pintype "input"))
      (node (ref "IC12") (pin "5") (pinfunction "I2_5") (pintype "input"))
      (node (ref "IC12") (pin "9") (pinfunction "I0_9") (pintype "input"))
      (node (ref "IC14") (pin "5") (pinfunction "I2_5") (pintype "input"))
    )
    (net (code "192") (name "~{MIRDY}") (class "Default")
      (node (ref "IC14") (pin "8") (pinfunction "O_8") (pintype "output"))
      (node (ref "IC16") (pin "5") (pinfunction "I1_5") (pintype "input"))
      (node (ref "IC17") (pin "12") (pinfunction "D_12") (pintype "input"))
    )
    (net (code "193") (name "~{MXRDY}") (class "Default")
      (node (ref "IC14") (pin "12") (pinfunction "O_12") (pintype "output"))
      (node (ref "IC16") (pin "4") (pinfunction "I0_4") (pintype "input"))
      (node (ref "IC17") (pin "2") (pinfunction "D_2") (pintype "input"))
    )
    (net (code "194") (name "~{MYIO}") (class "Default")
      (node (ref "IC10") (pin "6") (pinfunction "O_6") (pintype "output"))
      (node (ref "IC19") (pin "2") (pinfunction "D1_2") (pintype "input"))
    )
    (net (code "195") (name "~{NOEOT}") (class "Default")
      (node (ref "IC21") (pin "13") (pinfunction "O_13") (pintype "output"))
      (node (ref "IC25") (pin "13") (pinfunction "~{MR}_13") (pintype "input"))
    )
    (net (code "196") (name "~{RBUF}") (class "Default")
      (node (ref "IC18") (pin "6") (pinfunction "O_6") (pintype "output"))
      (node (ref "IC20") (pin "18") (pinfunction "~{DRR}_18") (pintype "input"))
    )
    (net (code "197") (name "~{RIRQ}") (class "Default")
      (node (ref "IC11") (pin "1") (pinfunction "I0_1") (pintype "input"))
      (node (ref "IC17") (pin "5") (pinfunction "Q_5") (pintype "output"))
    )
    (net (code "198") (name "~{RRUN}") (class "Default")
      (node (ref "IC21") (pin "11") (pinfunction "I0_11") (pintype "input"))
      (node (ref "IC22") (pin "6") (pinfunction "~{Q}_6") (pintype "output"))
      (node (ref "ZD4") (pin "A") (pinfunction "A_A") (pintype "passive"))
    )
    (net (code "199") (name "~{RSTOP}") (class "Default")
      (node (ref "IC21") (pin "1") (pinfunction "O_1") (pintype "output"))
      (node (ref "IC22") (pin "1") (pinfunction "CLR_1") (pintype "input"))
    )
    (net (code "200") (name "~{RXEIA}") (class "Default")
      (node (ref "IC23") (pin "1") (pinfunction "I_1") (pintype "input"))
      (node (ref "SV1") (pin "12") (pinfunction "12_12") (pintype "passive"))
    )
    (net (code "201") (name "~{SBRK}") (class "Default")
      (node (ref "IC22") (pin "8") (pinfunction "~{Q}_8") (pintype "output"))
      (node (ref "IC26") (pin "10") (pinfunction "I1_10") (pintype "input"))
    )
    (net (code "202") (name "~{SYNC}") (class "Default")
      (node (ref "IC19") (pin "13") (pinfunction "C12_13") (pintype "input"))
      (node (ref "IC19") (pin "4") (pinfunction "C34_4") (pintype "input"))
      (node (ref "IC2") (pin "3") (pinfunction "Y4_3") (pintype "tri_state"))
    )
    (net (code "203") (name "~{TXEIA}") (class "Default")
      (node (ref "C1") (pin "1") (pinfunction "1_1") (pintype "passive"))
      (node (ref "IC24") (pin "6") (pinfunction "O_6") (pintype "output"))
      (node (ref "SV1") (pin "11") (pinfunction "11_11") (pintype "passive"))
    )
    (net (code "204") (name "~{XBUF}") (class "Default")
      (node (ref "IC18") (pin "8") (pinfunction "O_8") (pintype "output"))
      (node (ref "IC20") (pin "23") (pinfunction "~{TBRL}_23") (pintype "input"))
    )
    (net (code "205") (name "~{XIAKI}") (class "Default")
      (node (ref "IC11") (pin "5") (pinfunction "I1_5") (pintype "input"))
      (node (ref "IC15") (pin "1") (pinfunction "CLR_1") (pintype "input"))
      (node (ref "IC16") (pin "8") (pinfunction "O_8") (pintype "output"))
    )
    (net (code "206") (name "~{XIRQ}") (class "Default")
      (node (ref "IC11") (pin "2") (pinfunction "I1_2") (pintype "input"))
      (node (ref "IC17") (pin "9") (pinfunction "Q_9") (pintype "output"))
      (node (ref "IC18") (pin "13") (pinfunction "I2_13") (pintype "input"))
      (node (ref "IC6") (pin "2") (pinfunction "1A_2") (pintype "input"))
    )
  )
)
